# FlexEval.net
KiCad netlist of a schematic drawn in EAGLE
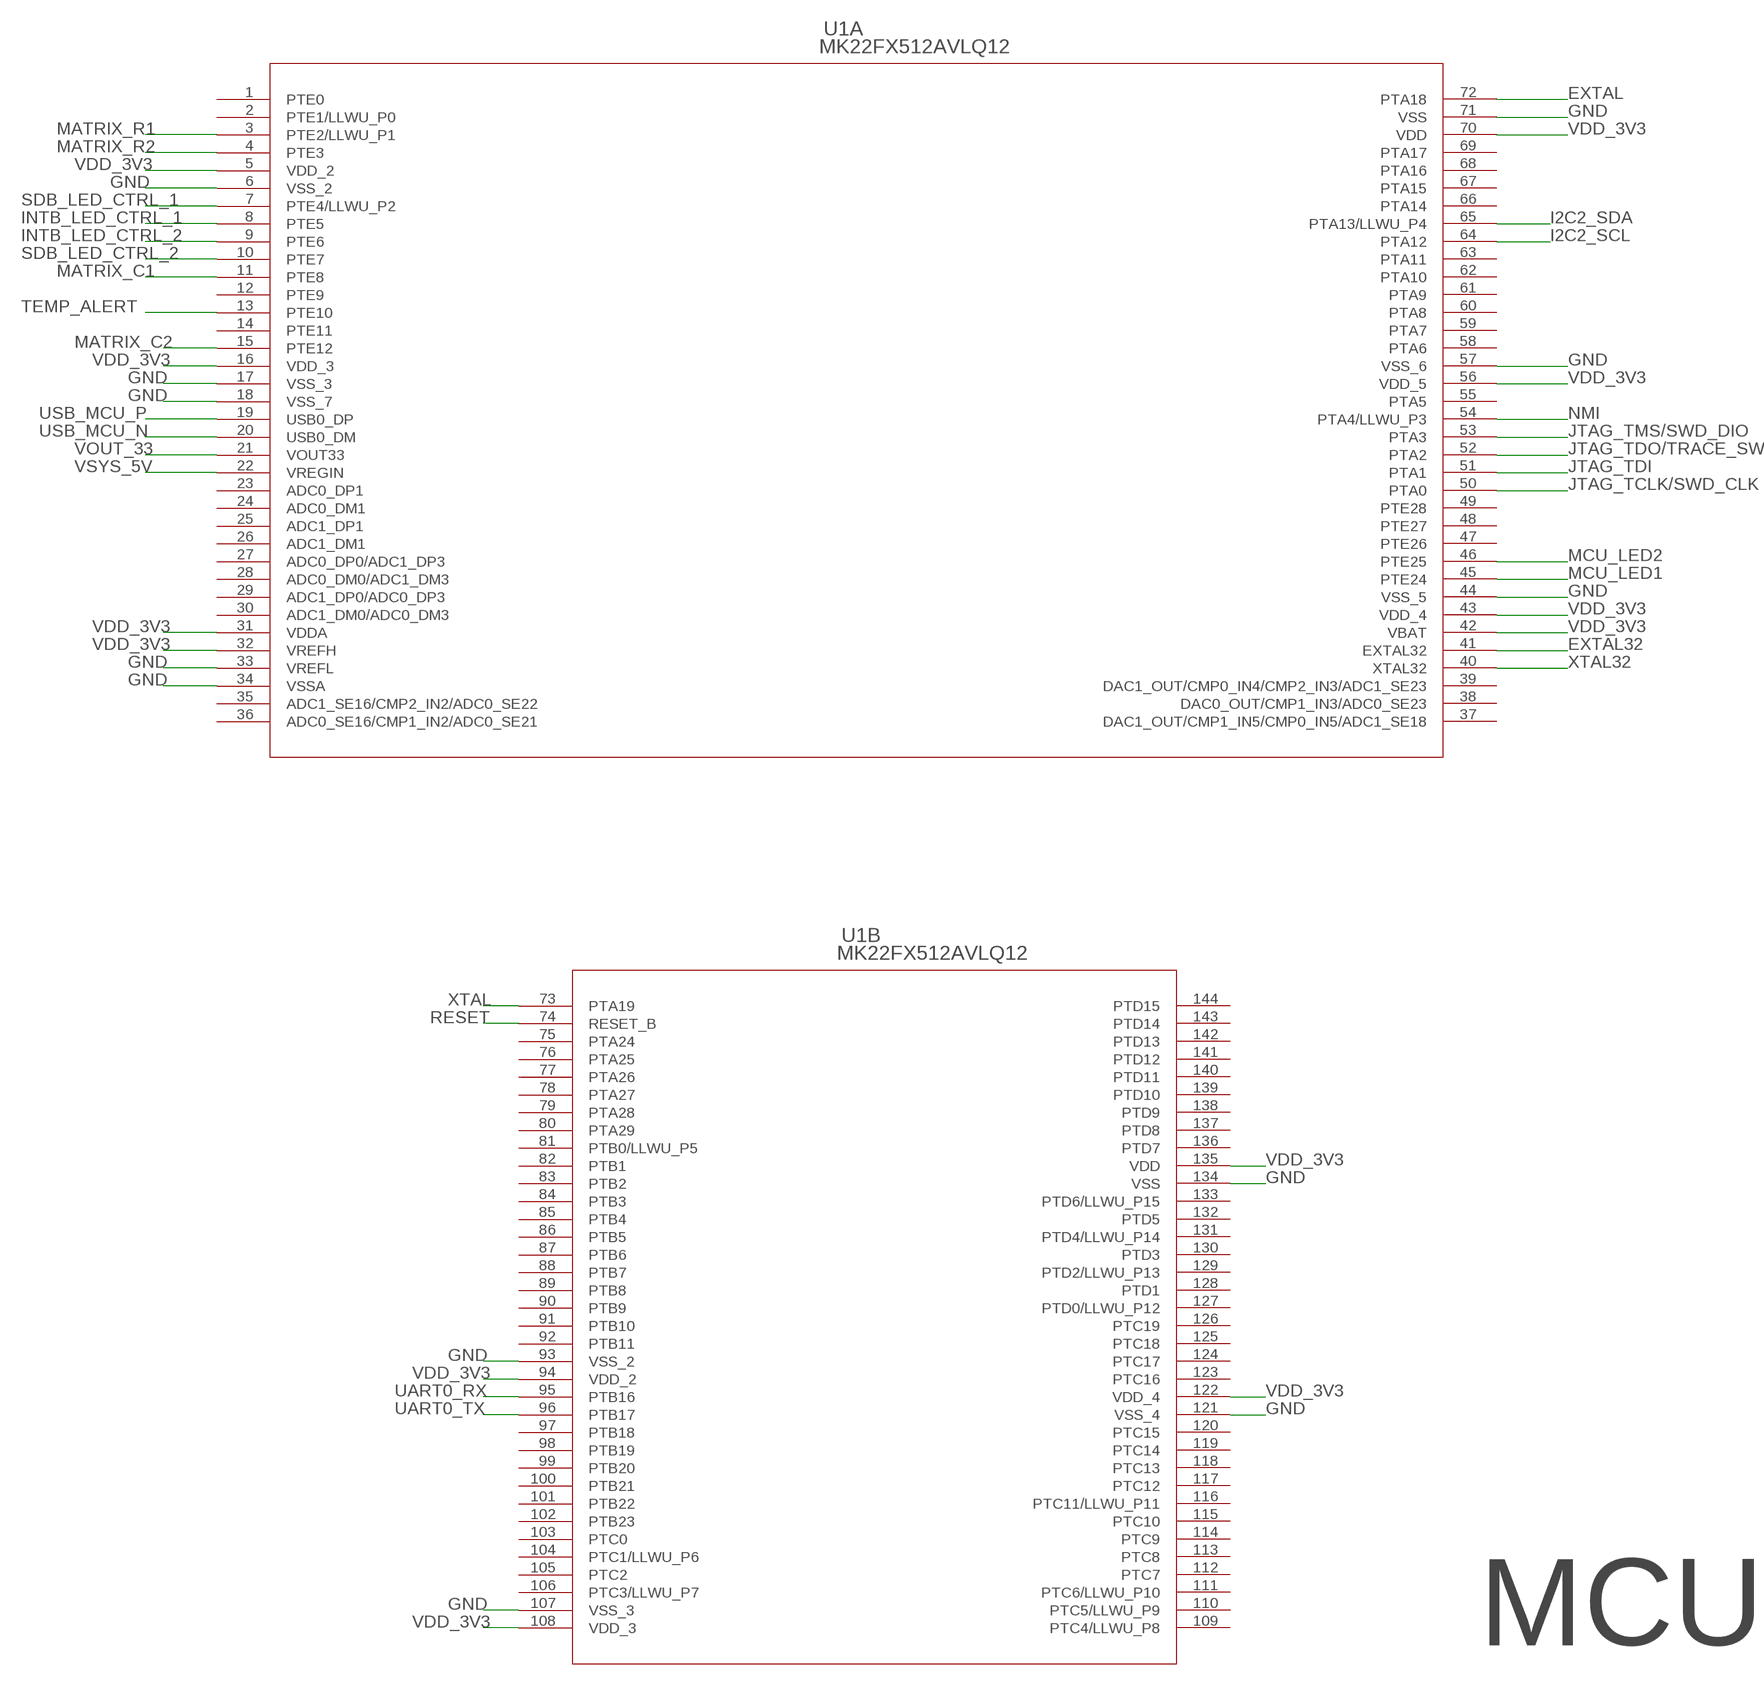
[diagram p0: schematic, sheet 1]
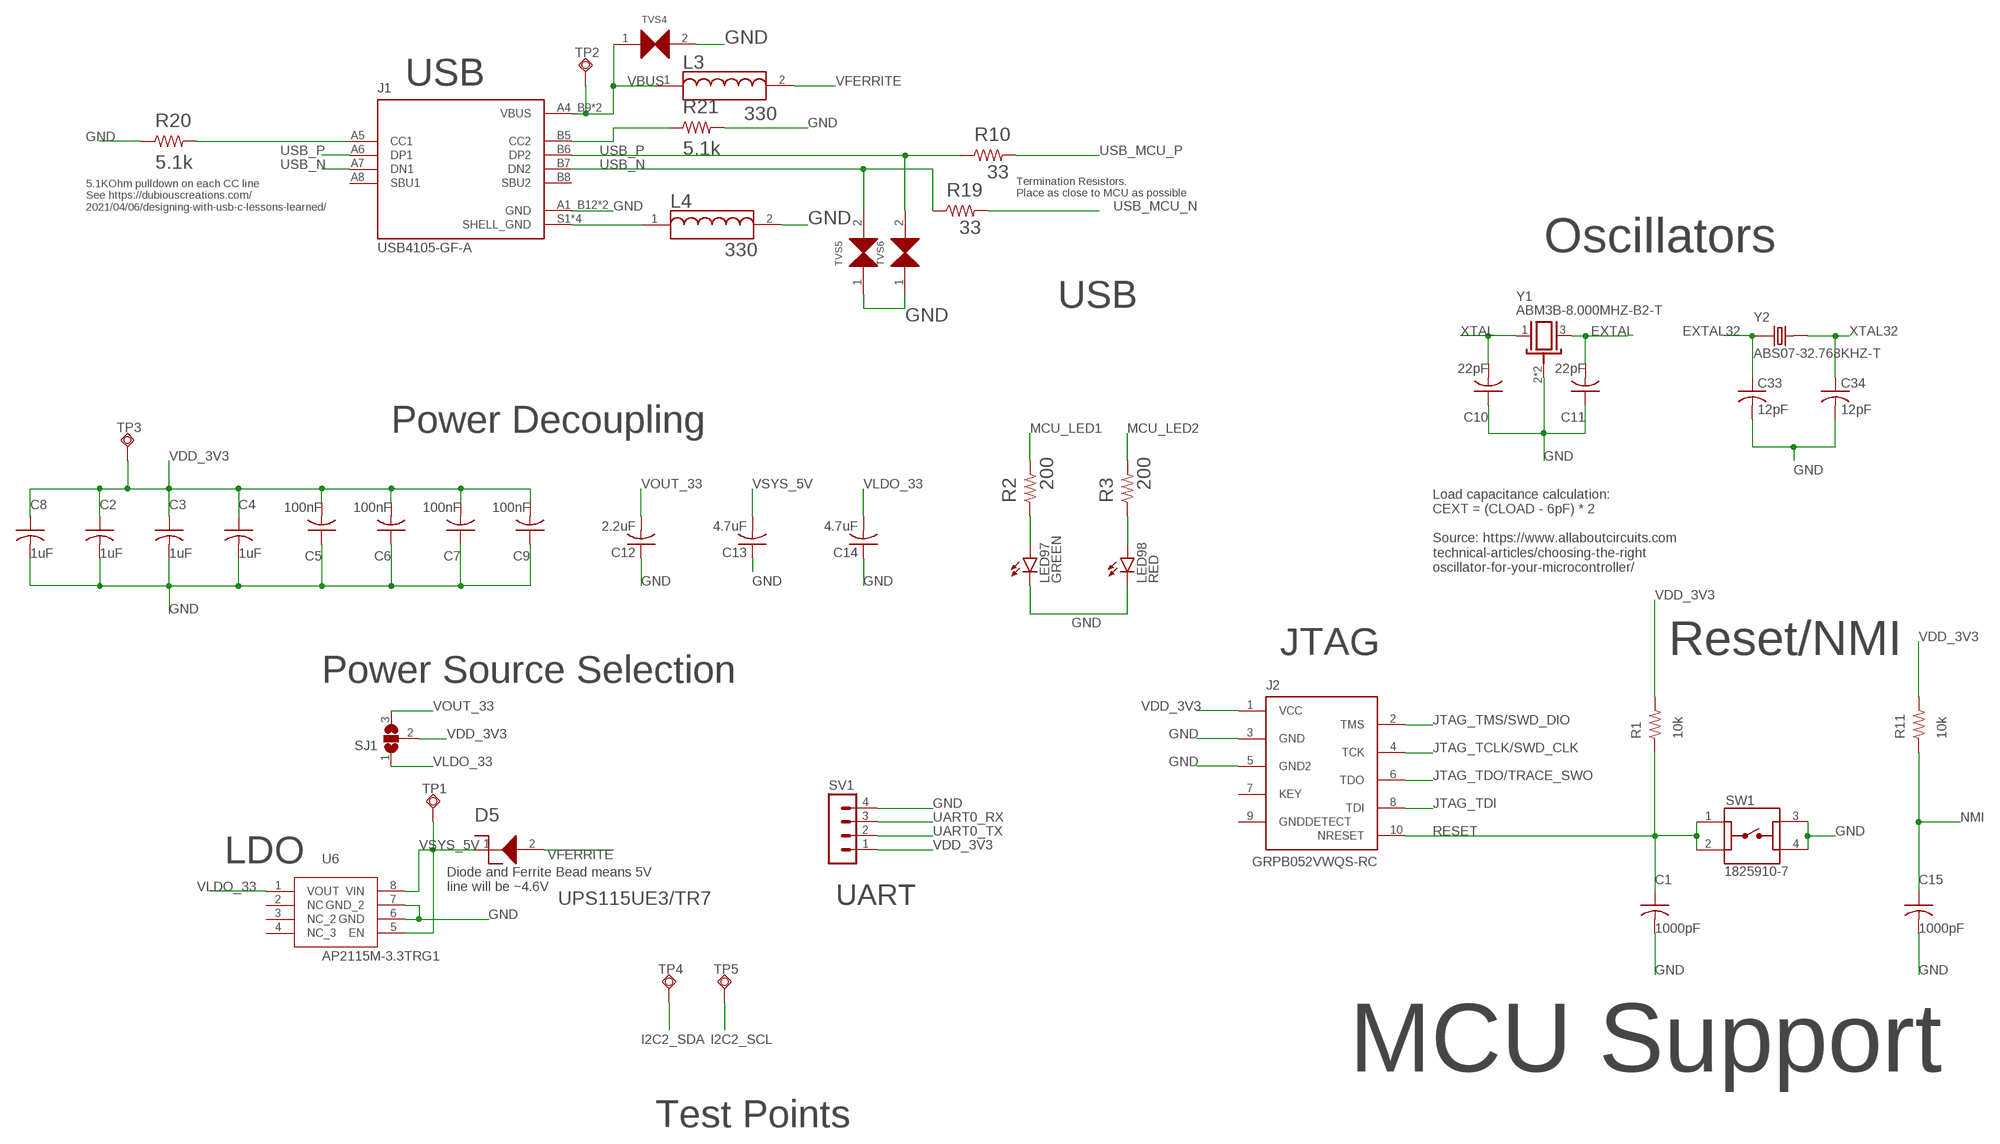
[diagram p1: schematic, sheet 2]
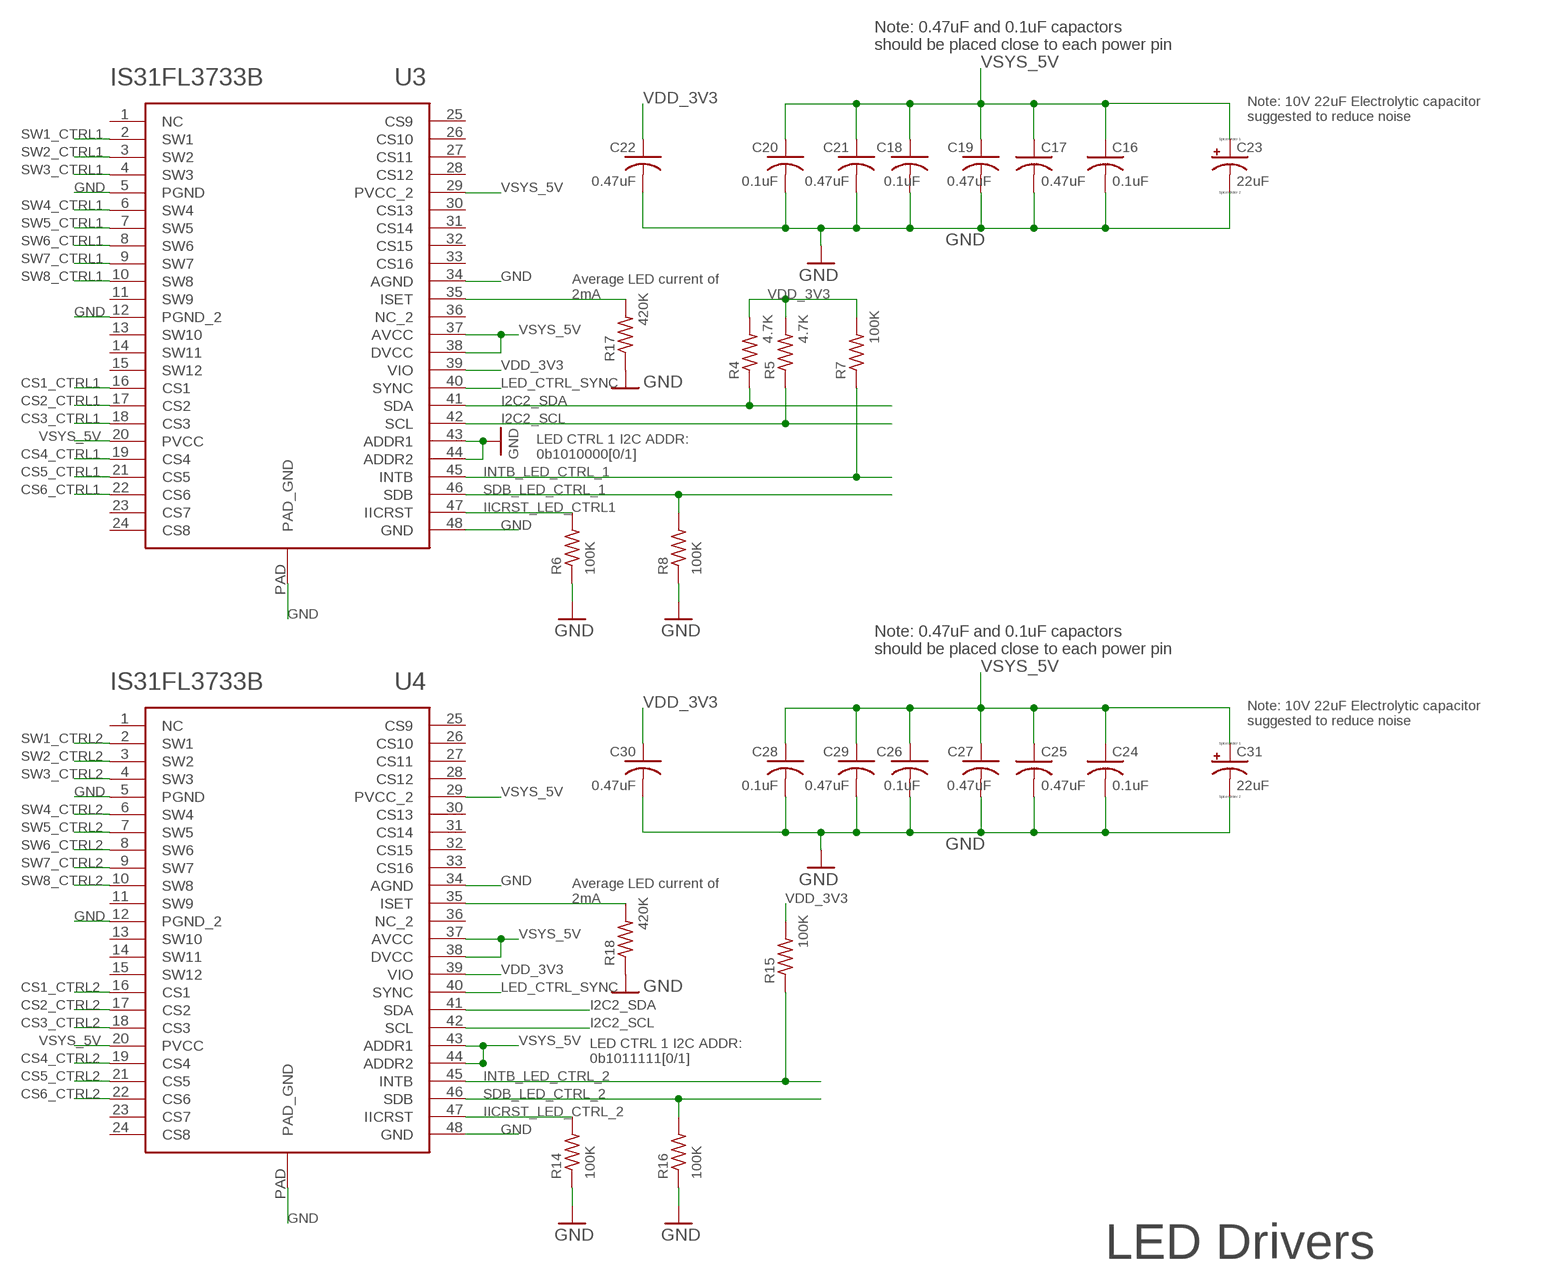
[diagram p2: schematic, sheet 3]
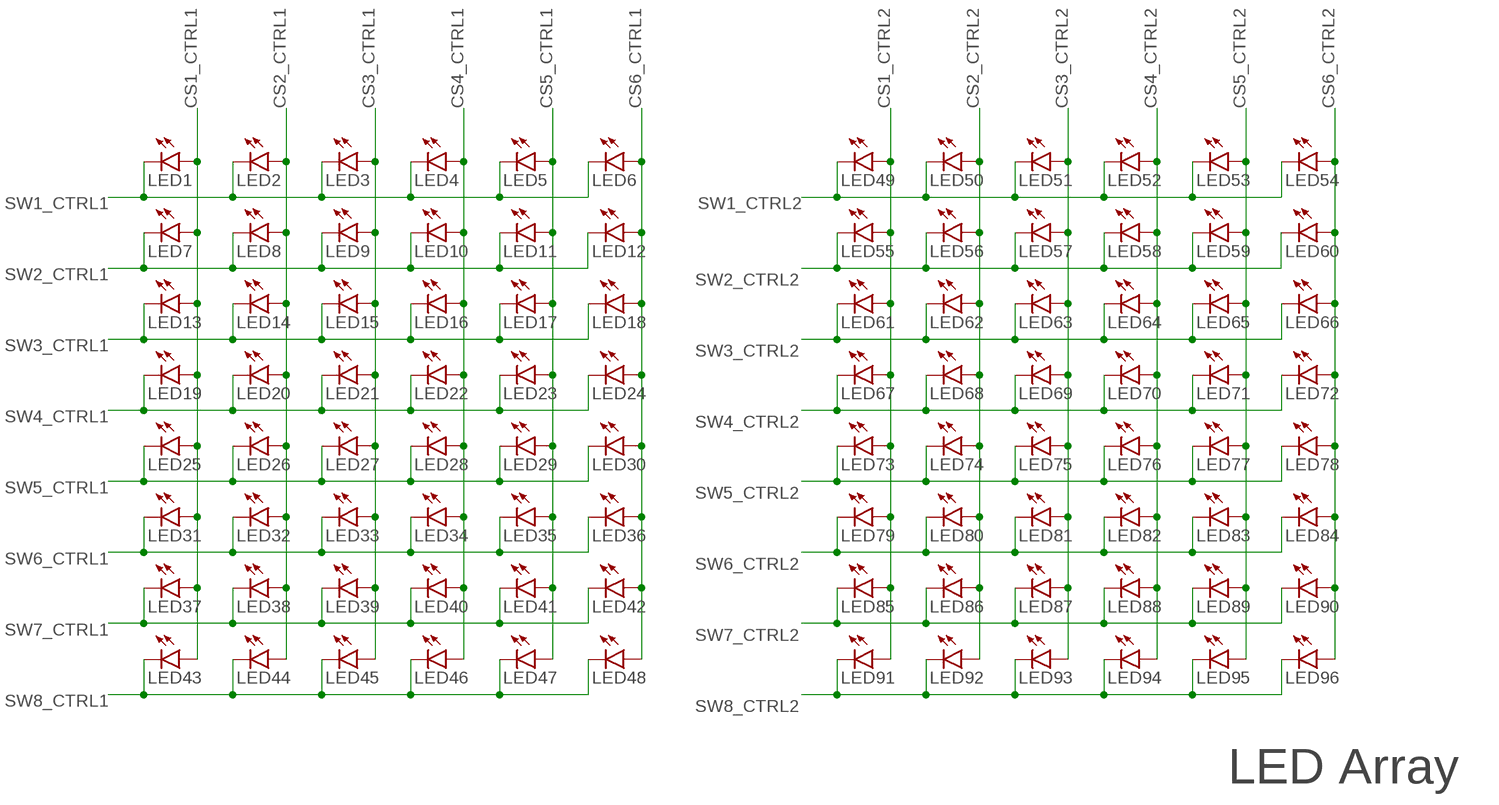
[diagram p3: schematic, sheet 4]
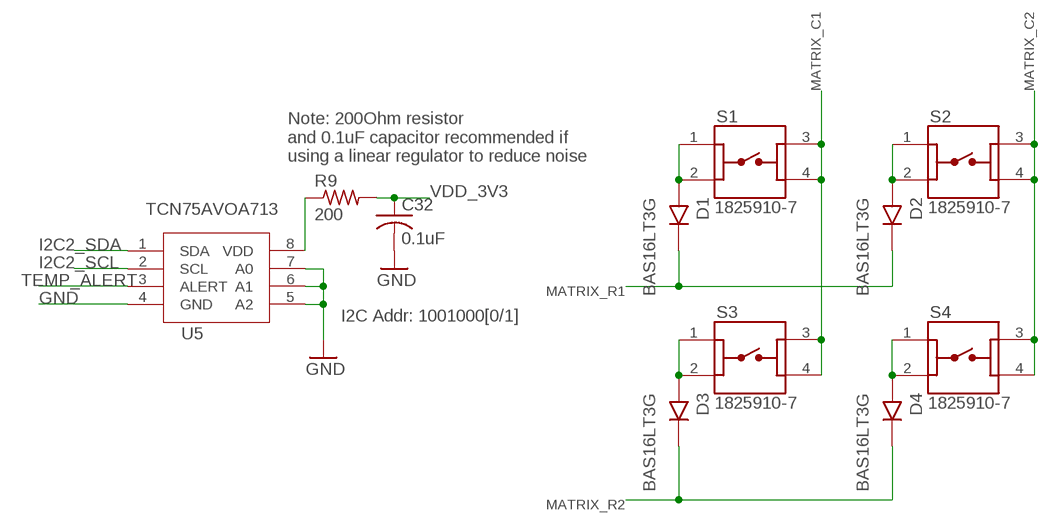
[diagram p4: schematic, sheet 5]

(export (version "E")
  (design (tool "Eeschema 10.0.6"))
  (components
    (comp (ref "C1")
      (value "1000pF")
      (footprint "eagle-import:C1206")
      (libsource (lib "eagle-import") (part "C-USC1206"))
    )
    (comp (ref "C2")
      (value "1uF")
      (footprint "eagle-import:C1206")
      (libsource (lib "eagle-import") (part "C-USC1206"))
    )
    (comp (ref "C3")
      (value "1uF")
      (footprint "eagle-import:C1206")
      (libsource (lib "eagle-import") (part "C-USC1206"))
    )
    (comp (ref "C4")
      (value "1uF")
      (footprint "eagle-import:C1206")
      (libsource (lib "eagle-import") (part "C-USC1206"))
    )
    (comp (ref "C5")
      (value "100nF")
      (footprint "eagle-import:C1206")
      (libsource (lib "eagle-import") (part "C-USC1206"))
    )
    (comp (ref "C6")
      (value "100nF")
      (footprint "eagle-import:C1206")
      (libsource (lib "eagle-import") (part "C-USC1206"))
    )
    (comp (ref "C7")
      (value "100nF")
      (footprint "eagle-import:C1206")
      (libsource (lib "eagle-import") (part "C-USC1206"))
    )
    (comp (ref "C8")
      (value "1uF")
      (footprint "eagle-import:C1206")
      (libsource (lib "eagle-import") (part "C-USC1206"))
    )
    (comp (ref "C9")
      (value "100nF")
      (footprint "eagle-import:C1206")
      (libsource (lib "eagle-import") (part "C-USC1206"))
    )
    (comp (ref "C10")
      (value "22pF")
      (footprint "eagle-import:C1206")
      (libsource (lib "eagle-import") (part "C-USC1206"))
    )
    (comp (ref "C11")
      (value "22pF")
      (footprint "eagle-import:C1206")
      (libsource (lib "eagle-import") (part "C-USC1206"))
    )
    (comp (ref "C12")
      (value "2.2uF")
      (footprint "eagle-import:C0805")
      (libsource (lib "eagle-import") (part "C-USC0805"))
    )
    (comp (ref "C13")
      (value "4.7uF")
      (footprint "eagle-import:C0805")
      (libsource (lib "eagle-import") (part "C-USC0805"))
    )
    (comp (ref "C14")
      (value "4.7uF")
      (footprint "eagle-import:C0805")
      (libsource (lib "eagle-import") (part "C-USC0805"))
    )
    (comp (ref "C15")
      (value "1000pF")
      (footprint "eagle-import:C1206")
      (libsource (lib "eagle-import") (part "C-USC1206"))
    )
    (comp (ref "C33")
      (value "12pF")
      (footprint "eagle-import:C0805")
      (libsource (lib "eagle-import") (part "C-USC0805"))
    )
    (comp (ref "C34")
      (value "12pF")
      (footprint "eagle-import:C0805")
      (libsource (lib "eagle-import") (part "C-USC0805"))
    )
    (comp (ref "D5")
      (value "UPS115UE3/TR7")
      (footprint "eagle-import:UPS115UE3_TR7")
      (libsource (lib "eagle-import") (part "UPS115UE3/TR7"))
    )
    (comp (ref "J1")
      (value "USB4105-GF-A")
      (footprint "eagle-import:GCT_USB4105-GF-A")
      (fields (field (name "MF") "GCT"))
      (libsource (lib "eagle-import") (part "USB4105-GF-A"))
    )
    (comp (ref "J2")
      (value "GRPB052VWQS-RC")
      (footprint "eagle-import:DEBUG")
      (fields (field (name "MF") "Sullins Connector"))
      (libsource (lib "eagle-import") (part "GRPB052VWQS-RC"))
    )
    (comp (ref "L3")
      (value "330")
      (footprint "eagle-import:78285333")
      (libsource (lib "eagle-import") (part "782853331SMD"))
    )
    (comp (ref "L4")
      (value "330")
      (footprint "eagle-import:78285333")
      (libsource (lib "eagle-import") (part "782853331SMD"))
    )
    (comp (ref "LED97")
      (value "GREEN")
      (footprint "eagle-import:SML1206")
      (libsource (lib "eagle-import") (part "LEDSML1206"))
    )
    (comp (ref "LED98")
      (value "RED")
      (footprint "eagle-import:SML1206")
      (libsource (lib "eagle-import") (part "LEDSML1206"))
    )
    (comp (ref "R1")
      (value "10k")
      (footprint "eagle-import:R1206")
      (libsource (lib "eagle-import") (part "R-US_R1206"))
    )
    (comp (ref "R2")
      (value "200")
      (footprint "eagle-import:R0805")
      (libsource (lib "eagle-import") (part "R-US_R0805"))
    )
    (comp (ref "R3")
      (value "200")
      (footprint "eagle-import:R0805")
      (libsource (lib "eagle-import") (part "R-US_R0805"))
    )
    (comp (ref "R10")
      (value "33")
      (footprint "eagle-import:R0805")
      (libsource (lib "eagle-import") (part "R-US_R0805"))
    )
    (comp (ref "R11")
      (value "10k")
      (footprint "eagle-import:R1206")
      (libsource (lib "eagle-import") (part "R-US_R1206"))
    )
    (comp (ref "R19")
      (value "33")
      (footprint "eagle-import:R0805")
      (libsource (lib "eagle-import") (part "R-US_R0805"))
    )
    (comp (ref "R20")
      (value "5.1k")
      (footprint "eagle-import:R0805")
      (libsource (lib "eagle-import") (part "R-US_R0805"))
    )
    (comp (ref "R21")
      (value "5.1k")
      (footprint "eagle-import:R0805")
      (libsource (lib "eagle-import") (part "R-US_R0805"))
    )
    (comp (ref "SJ1")
      (value "SJ2W")
      (footprint "eagle-import:SJ_2")
      (libsource (lib "eagle-import") (part "SJ2W"))
    )
    (comp (ref "SV1")
      (value "MA04-1")
      (footprint "eagle-import:MA04-1")
      (libsource (lib "eagle-import") (part "MA04-1"))
    )
    (comp (ref "SW1")
      (value "1825910-7")
      (footprint "eagle-import:SW_1825910-7")
      (fields (field (name "MF") "TE Connectivity"))
      (libsource (lib "eagle-import") (part "1825910-7"))
    )
    (comp (ref "TP1")
      (value "TPSQTP20R")
      (footprint "eagle-import:TP20R")
      (libsource (lib "eagle-import") (part "TPSQTP20R"))
    )
    (comp (ref "TP2")
      (value "TPSQTP20R")
      (footprint "eagle-import:TP20R")
      (libsource (lib "eagle-import") (part "TPSQTP20R"))
    )
    (comp (ref "TP3")
      (value "TPSQTP20R")
      (footprint "eagle-import:TP20R")
      (libsource (lib "eagle-import") (part "TPSQTP20R"))
    )
    (comp (ref "TP4")
      (value "TPSQTP20R")
      (footprint "eagle-import:TP20R")
      (libsource (lib "eagle-import") (part "TPSQTP20R"))
    )
    (comp (ref "TP5")
      (value "TPSQTP20R")
      (footprint "eagle-import:TP20R")
      (libsource (lib "eagle-import") (part "TPSQTP20R"))
    )
    (comp (ref "TVS4")
      (value "0603ESDA2-TR2")
      (footprint "eagle-import:0603ESDA2-TR2")
      (libsource (lib "eagle-import") (part "0603ESDA2-TR2"))
    )
    (comp (ref "TVS5")
      (value "0603ESDA2-TR2")
      (footprint "eagle-import:0603ESDA2-TR2")
      (libsource (lib "eagle-import") (part "0603ESDA2-TR2"))
    )
    (comp (ref "TVS6")
      (value "0603ESDA2-TR2")
      (footprint "eagle-import:0603ESDA2-TR2")
      (libsource (lib "eagle-import") (part "0603ESDA2-TR2"))
    )
    (comp (ref "U6")
      (value "AP2115M-3.3TRG1")
      (footprint "eagle-import:SOIC127P600X175-8N")
      (libsource (lib "eagle-import") (part "AP2115M-3.3TRG1"))
    )
    (comp (ref "Y1")
      (value "ABM3B-8.000MHZ-B2-T")
      (footprint "eagle-import:OSC_ABM3B-8.000MHZ-B2-T")
      (fields (field (name "MF") "Abracon"))
      (libsource (lib "eagle-import") (part "ABM3B-8.000MHZ-B2-T"))
    )
    (comp (ref "Y2")
      (value "ABS07-32.768KHZ-T")
      (footprint "eagle-import:XTAL_ABS07-32.768KHZ-T")
      (fields (field (name "MF") "Abracon"))
      (libsource (lib "eagle-import") (part "ABS07-32.768KHZ-T"))
    )
    (comp (ref "C32")
      (value "0.1uF")
      (footprint "eagle-import:C0805")
      (libsource (lib "eagle-import") (part "C-USC0805"))
    )
    (comp (ref "D1")
      (value "BAS16LT3G")
      (footprint "eagle-import:SOT95P240X111-3N")
      (fields (field (name "MF") "ON Semiconductor"))
      (libsource (lib "eagle-import") (part "BAS16LT3G"))
    )
    (comp (ref "D2")
      (value "BAS16LT3G")
      (footprint "eagle-import:SOT95P240X111-3N")
      (fields (field (name "MF") "ON Semiconductor"))
      (libsource (lib "eagle-import") (part "BAS16LT3G"))
    )
    (comp (ref "D3")
      (value "BAS16LT3G")
      (footprint "eagle-import:SOT95P240X111-3N")
      (fields (field (name "MF") "ON Semiconductor"))
      (libsource (lib "eagle-import") (part "BAS16LT3G"))
    )
    (comp (ref "D4")
      (value "BAS16LT3G")
      (footprint "eagle-import:SOT95P240X111-3N")
      (fields (field (name "MF") "ON Semiconductor"))
      (libsource (lib "eagle-import") (part "BAS16LT3G"))
    )
    (comp (ref "R9")
      (value "200")
      (footprint "eagle-import:R0805")
      (libsource (lib "eagle-import") (part "R-US_R0805"))
    )
    (comp (ref "S1")
      (value "1825910-7")
      (footprint "eagle-import:SW_1825910-7")
      (fields (field (name "MF") "TE Connectivity"))
      (libsource (lib "eagle-import") (part "1825910-7"))
    )
    (comp (ref "S2")
      (value "1825910-7")
      (footprint "eagle-import:SW_1825910-7")
      (fields (field (name "MF") "TE Connectivity"))
      (libsource (lib "eagle-import") (part "1825910-7"))
    )
    (comp (ref "S3")
      (value "1825910-7")
      (footprint "eagle-import:SW_1825910-7")
      (fields (field (name "MF") "TE Connectivity"))
      (libsource (lib "eagle-import") (part "1825910-7"))
    )
    (comp (ref "S4")
      (value "1825910-7")
      (footprint "eagle-import:SW_1825910-7")
      (fields (field (name "MF") "TE Connectivity"))
      (libsource (lib "eagle-import") (part "1825910-7"))
    )
    (comp (ref "U5")
      (value "SOIC127P600X175-8N")
      (footprint "eagle-import:SOIC127P600X175-8N")
      (fields (field (name "MANUFACTURER") "hotchip"))
      (libsource (lib "eagle-import") (part "SOIC127P600X175-8N"))
    )
    (comp (ref "U1")
      (value "MK22FX512AVLQ12")
      (footprint "eagle-import:LQFP-144_20X20X1.6")
      (libsource (lib "eagle-import") (part "MK22FX512AVLQ12"))
    )
    (comp (ref "C16")
      (value "0.1uF")
      (footprint "eagle-import:C0805")
      (libsource (lib "eagle-import") (part "C-USC0805"))
    )
    (comp (ref "C17")
      (value "0.47uF")
      (footprint "eagle-import:C0805")
      (libsource (lib "eagle-import") (part "C-USC0805"))
    )
    (comp (ref "C18")
      (value "0.1uF")
      (footprint "eagle-import:C0805")
      (libsource (lib "eagle-import") (part "C-USC0805"))
    )
    (comp (ref "C19")
      (value "0.47uF")
      (footprint "eagle-import:C0805")
      (libsource (lib "eagle-import") (part "C-USC0805"))
    )
    (comp (ref "C20")
      (value "0.1uF")
      (footprint "eagle-import:C0805")
      (libsource (lib "eagle-import") (part "C-USC0805"))
    )
    (comp (ref "C21")
      (value "0.47uF")
      (footprint "eagle-import:C0805")
      (libsource (lib "eagle-import") (part "C-USC0805"))
    )
    (comp (ref "C22")
      (value "0.47uF")
      (footprint "eagle-import:C0805")
      (libsource (lib "eagle-import") (part "C-USC0805"))
    )
    (comp (ref "C23")
      (value "22uF")
      (footprint "eagle-import:860020672011")
      (libsource (lib "eagle-import") (part "860020672011"))
    )
    (comp (ref "C24")
      (value "0.1uF")
      (footprint "eagle-import:C0805")
      (libsource (lib "eagle-import") (part "C-USC0805"))
    )
    (comp (ref "C25")
      (value "0.47uF")
      (footprint "eagle-import:C0805")
      (libsource (lib "eagle-import") (part "C-USC0805"))
    )
    (comp (ref "C26")
      (value "0.1uF")
      (footprint "eagle-import:C0805")
      (libsource (lib "eagle-import") (part "C-USC0805"))
    )
    (comp (ref "C27")
      (value "0.47uF")
      (footprint "eagle-import:C0805")
      (libsource (lib "eagle-import") (part "C-USC0805"))
    )
    (comp (ref "C28")
      (value "0.1uF")
      (footprint "eagle-import:C0805")
      (libsource (lib "eagle-import") (part "C-USC0805"))
    )
    (comp (ref "C29")
      (value "0.47uF")
      (footprint "eagle-import:C0805")
      (libsource (lib "eagle-import") (part "C-USC0805"))
    )
    (comp (ref "C30")
      (value "0.47uF")
      (footprint "eagle-import:C0805")
      (libsource (lib "eagle-import") (part "C-USC0805"))
    )
    (comp (ref "C31")
      (value "22uF")
      (footprint "eagle-import:860020672011")
      (libsource (lib "eagle-import") (part "860020672011"))
    )
    (comp (ref "R4")
      (value "4.7K")
      (footprint "eagle-import:R0805")
      (libsource (lib "eagle-import") (part "R-US_R0805"))
    )
    (comp (ref "R5")
      (value "4.7K")
      (footprint "eagle-import:R0805")
      (libsource (lib "eagle-import") (part "R-US_R0805"))
    )
    (comp (ref "R6")
      (value "100K")
      (footprint "eagle-import:R0805")
      (libsource (lib "eagle-import") (part "R-US_R0805"))
    )
    (comp (ref "R7")
      (value "100K")
      (footprint "eagle-import:R0805")
      (libsource (lib "eagle-import") (part "R-US_R0805"))
    )
    (comp (ref "R8")
      (value "100K")
      (footprint "eagle-import:R0805")
      (libsource (lib "eagle-import") (part "R-US_R0805"))
    )
    (comp (ref "R14")
      (value "100K")
      (footprint "eagle-import:R0805")
      (libsource (lib "eagle-import") (part "R-US_R0805"))
    )
    (comp (ref "R15")
      (value "100K")
      (footprint "eagle-import:R0805")
      (libsource (lib "eagle-import") (part "R-US_R0805"))
    )
    (comp (ref "R16")
      (value "100K")
      (footprint "eagle-import:R0805")
      (libsource (lib "eagle-import") (part "R-US_R0805"))
    )
    (comp (ref "R17")
      (value "420K")
      (footprint "eagle-import:R0805")
      (libsource (lib "eagle-import") (part "R-US_R0805"))
    )
    (comp (ref "R18")
      (value "420K")
      (footprint "eagle-import:R0805")
      (libsource (lib "eagle-import") (part "R-US_R0805"))
    )
    (comp (ref "U3")
      (value "IS31FL3733B-TQLS4")
      (footprint "eagle-import:IS31FL3733B-TQLS4")
      (libsource (lib "eagle-import") (part "IS31FL3733B-TQLS4"))
    )
    (comp (ref "U4")
      (value "IS31FL3733B-TQLS4")
      (footprint "eagle-import:IS31FL3733B-TQLS4")
      (libsource (lib "eagle-import") (part "IS31FL3733B-TQLS4"))
    )
    (comp (ref "LED1")
      (value "LED3MM")
      (footprint "eagle-import:LED3MM")
      (libsource (lib "eagle-import") (part "LED3MM"))
    )
    (comp (ref "LED2")
      (value "LED3MM")
      (footprint "eagle-import:LED3MM")
      (libsource (lib "eagle-import") (part "LED3MM"))
    )
    (comp (ref "LED3")
      (value "LED3MM")
      (footprint "eagle-import:LED3MM")
      (libsource (lib "eagle-import") (part "LED3MM"))
    )
    (comp (ref "LED4")
      (value "LED3MM")
      (footprint "eagle-import:LED3MM")
      (libsource (lib "eagle-import") (part "LED3MM"))
    )
    (comp (ref "LED5")
      (value "LED3MM")
      (footprint "eagle-import:LED3MM")
      (libsource (lib "eagle-import") (part "LED3MM"))
    )
    (comp (ref "LED6")
      (value "LED3MM")
      (footprint "eagle-import:LED3MM")
      (libsource (lib "eagle-import") (part "LED3MM"))
    )
    (comp (ref "LED7")
      (value "LED3MM")
      (footprint "eagle-import:LED3MM")
      (libsource (lib "eagle-import") (part "LED3MM"))
    )
    (comp (ref "LED8")
      (value "LED3MM")
      (footprint "eagle-import:LED3MM")
      (libsource (lib "eagle-import") (part "LED3MM"))
    )
    (comp (ref "LED9")
      (value "LED3MM")
      (footprint "eagle-import:LED3MM")
      (libsource (lib "eagle-import") (part "LED3MM"))
    )
    (comp (ref "LED10")
      (value "LED3MM")
      (footprint "eagle-import:LED3MM")
      (libsource (lib "eagle-import") (part "LED3MM"))
    )
    (comp (ref "LED11")
      (value "LED3MM")
      (footprint "eagle-import:LED3MM")
      (libsource (lib "eagle-import") (part "LED3MM"))
    )
    (comp (ref "LED12")
      (value "LED3MM")
      (footprint "eagle-import:LED3MM")
      (libsource (lib "eagle-import") (part "LED3MM"))
    )
    (comp (ref "LED13")
      (value "LED3MM")
      (footprint "eagle-import:LED3MM")
      (libsource (lib "eagle-import") (part "LED3MM"))
    )
    (comp (ref "LED14")
      (value "LED3MM")
      (footprint "eagle-import:LED3MM")
      (libsource (lib "eagle-import") (part "LED3MM"))
    )
    (comp (ref "LED15")
      (value "LED3MM")
      (footprint "eagle-import:LED3MM")
      (libsource (lib "eagle-import") (part "LED3MM"))
    )
    (comp (ref "LED16")
      (value "LED3MM")
      (footprint "eagle-import:LED3MM")
      (libsource (lib "eagle-import") (part "LED3MM"))
    )
    (comp (ref "LED17")
      (value "LED3MM")
      (footprint "eagle-import:LED3MM")
      (libsource (lib "eagle-import") (part "LED3MM"))
    )
    (comp (ref "LED18")
      (value "LED3MM")
      (footprint "eagle-import:LED3MM")
      (libsource (lib "eagle-import") (part "LED3MM"))
    )
    (comp (ref "LED19")
      (value "LED3MM")
      (footprint "eagle-import:LED3MM")
      (libsource (lib "eagle-import") (part "LED3MM"))
    )
    (comp (ref "LED20")
      (value "LED3MM")
      (footprint "eagle-import:LED3MM")
      (libsource (lib "eagle-import") (part "LED3MM"))
    )
    (comp (ref "LED21")
      (value "LED3MM")
      (footprint "eagle-import:LED3MM")
      (libsource (lib "eagle-import") (part "LED3MM"))
    )
    (comp (ref "LED22")
      (value "LED3MM")
      (footprint "eagle-import:LED3MM")
      (libsource (lib "eagle-import") (part "LED3MM"))
    )
    (comp (ref "LED23")
      (value "LED3MM")
      (footprint "eagle-import:LED3MM")
      (libsource (lib "eagle-import") (part "LED3MM"))
    )
    (comp (ref "LED24")
      (value "LED3MM")
      (footprint "eagle-import:LED3MM")
      (libsource (lib "eagle-import") (part "LED3MM"))
    )
    (comp (ref "LED25")
      (value "LED3MM")
      (footprint "eagle-import:LED3MM")
      (libsource (lib "eagle-import") (part "LED3MM"))
    )
    (comp (ref "LED26")
      (value "LED3MM")
      (footprint "eagle-import:LED3MM")
      (libsource (lib "eagle-import") (part "LED3MM"))
    )
    (comp (ref "LED27")
      (value "LED3MM")
      (footprint "eagle-import:LED3MM")
      (libsource (lib "eagle-import") (part "LED3MM"))
    )
    (comp (ref "LED28")
      (value "LED3MM")
      (footprint "eagle-import:LED3MM")
      (libsource (lib "eagle-import") (part "LED3MM"))
    )
    (comp (ref "LED29")
      (value "LED3MM")
      (footprint "eagle-import:LED3MM")
      (libsource (lib "eagle-import") (part "LED3MM"))
    )
    (comp (ref "LED30")
      (value "LED3MM")
      (footprint "eagle-import:LED3MM")
      (libsource (lib "eagle-import") (part "LED3MM"))
    )
    (comp (ref "LED31")
      (value "LED3MM")
      (footprint "eagle-import:LED3MM")
      (libsource (lib "eagle-import") (part "LED3MM"))
    )
    (comp (ref "LED32")
      (value "LED3MM")
      (footprint "eagle-import:LED3MM")
      (libsource (lib "eagle-import") (part "LED3MM"))
    )
    (comp (ref "LED33")
      (value "LED3MM")
      (footprint "eagle-import:LED3MM")
      (libsource (lib "eagle-import") (part "LED3MM"))
    )
    (comp (ref "LED34")
      (value "LED3MM")
      (footprint "eagle-import:LED3MM")
      (libsource (lib "eagle-import") (part "LED3MM"))
    )
    (comp (ref "LED35")
      (value "LED3MM")
      (footprint "eagle-import:LED3MM")
      (libsource (lib "eagle-import") (part "LED3MM"))
    )
    (comp (ref "LED36")
      (value "LED3MM")
      (footprint "eagle-import:LED3MM")
      (libsource (lib "eagle-import") (part "LED3MM"))
    )
    (comp (ref "LED37")
      (value "LED3MM")
      (footprint "eagle-import:LED3MM")
      (libsource (lib "eagle-import") (part "LED3MM"))
    )
    (comp (ref "LED38")
      (value "LED3MM")
      (footprint "eagle-import:LED3MM")
      (libsource (lib "eagle-import") (part "LED3MM"))
    )
    (comp (ref "LED39")
      (value "LED3MM")
      (footprint "eagle-import:LED3MM")
      (libsource (lib "eagle-import") (part "LED3MM"))
    )
    (comp (ref "LED40")
      (value "LED3MM")
      (footprint "eagle-import:LED3MM")
      (libsource (lib "eagle-import") (part "LED3MM"))
    )
    (comp (ref "LED41")
      (value "LED3MM")
      (footprint "eagle-import:LED3MM")
      (libsource (lib "eagle-import") (part "LED3MM"))
    )
    (comp (ref "LED42")
      (value "LED3MM")
      (footprint "eagle-import:LED3MM")
      (libsource (lib "eagle-import") (part "LED3MM"))
    )
    (comp (ref "LED43")
      (value "LED3MM")
      (footprint "eagle-import:LED3MM")
      (libsource (lib "eagle-import") (part "LED3MM"))
    )
    (comp (ref "LED44")
      (value "LED3MM")
      (footprint "eagle-import:LED3MM")
      (libsource (lib "eagle-import") (part "LED3MM"))
    )
    (comp (ref "LED45")
      (value "LED3MM")
      (footprint "eagle-import:LED3MM")
      (libsource (lib "eagle-import") (part "LED3MM"))
    )
    (comp (ref "LED46")
      (value "LED3MM")
      (footprint "eagle-import:LED3MM")
      (libsource (lib "eagle-import") (part "LED3MM"))
    )
    (comp (ref "LED47")
      (value "LED3MM")
      (footprint "eagle-import:LED3MM")
      (libsource (lib "eagle-import") (part "LED3MM"))
    )
    (comp (ref "LED48")
      (value "LED3MM")
      (footprint "eagle-import:LED3MM")
      (libsource (lib "eagle-import") (part "LED3MM"))
    )
    (comp (ref "LED49")
      (value "LED3MM")
      (footprint "eagle-import:LED3MM")
      (libsource (lib "eagle-import") (part "LED3MM"))
    )
    (comp (ref "LED50")
      (value "LED3MM")
      (footprint "eagle-import:LED3MM")
      (libsource (lib "eagle-import") (part "LED3MM"))
    )
    (comp (ref "LED51")
      (value "LED3MM")
      (footprint "eagle-import:LED3MM")
      (libsource (lib "eagle-import") (part "LED3MM"))
    )
    (comp (ref "LED52")
      (value "LED3MM")
      (footprint "eagle-import:LED3MM")
      (libsource (lib "eagle-import") (part "LED3MM"))
    )
    (comp (ref "LED53")
      (value "LED3MM")
      (footprint "eagle-import:LED3MM")
      (libsource (lib "eagle-import") (part "LED3MM"))
    )
    (comp (ref "LED54")
      (value "LED3MM")
      (footprint "eagle-import:LED3MM")
      (libsource (lib "eagle-import") (part "LED3MM"))
    )
    (comp (ref "LED55")
      (value "LED3MM")
      (footprint "eagle-import:LED3MM")
      (libsource (lib "eagle-import") (part "LED3MM"))
    )
    (comp (ref "LED56")
      (value "LED3MM")
      (footprint "eagle-import:LED3MM")
      (libsource (lib "eagle-import") (part "LED3MM"))
    )
    (comp (ref "LED57")
      (value "LED3MM")
      (footprint "eagle-import:LED3MM")
      (libsource (lib "eagle-import") (part "LED3MM"))
    )
    (comp (ref "LED58")
      (value "LED3MM")
      (footprint "eagle-import:LED3MM")
      (libsource (lib "eagle-import") (part "LED3MM"))
    )
    (comp (ref "LED59")
      (value "LED3MM")
      (footprint "eagle-import:LED3MM")
      (libsource (lib "eagle-import") (part "LED3MM"))
    )
    (comp (ref "LED60")
      (value "LED3MM")
      (footprint "eagle-import:LED3MM")
      (libsource (lib "eagle-import") (part "LED3MM"))
    )
    (comp (ref "LED61")
      (value "LED3MM")
      (footprint "eagle-import:LED3MM")
      (libsource (lib "eagle-import") (part "LED3MM"))
    )
    (comp (ref "LED62")
      (value "LED3MM")
      (footprint "eagle-import:LED3MM")
      (libsource (lib "eagle-import") (part "LED3MM"))
    )
    (comp (ref "LED63")
      (value "LED3MM")
      (footprint "eagle-import:LED3MM")
      (libsource (lib "eagle-import") (part "LED3MM"))
    )
    (comp (ref "LED64")
      (value "LED3MM")
      (footprint "eagle-import:LED3MM")
      (libsource (lib "eagle-import") (part "LED3MM"))
    )
    (comp (ref "LED65")
      (value "LED3MM")
      (footprint "eagle-import:LED3MM")
      (libsource (lib "eagle-import") (part "LED3MM"))
    )
    (comp (ref "LED66")
      (value "LED3MM")
      (footprint "eagle-import:LED3MM")
      (libsource (lib "eagle-import") (part "LED3MM"))
    )
    (comp (ref "LED67")
      (value "LED3MM")
      (footprint "eagle-import:LED3MM")
      (libsource (lib "eagle-import") (part "LED3MM"))
    )
    (comp (ref "LED68")
      (value "LED3MM")
      (footprint "eagle-import:LED3MM")
      (libsource (lib "eagle-import") (part "LED3MM"))
    )
    (comp (ref "LED69")
      (value "LED3MM")
      (footprint "eagle-import:LED3MM")
      (libsource (lib "eagle-import") (part "LED3MM"))
    )
    (comp (ref "LED70")
      (value "LED3MM")
      (footprint "eagle-import:LED3MM")
      (libsource (lib "eagle-import") (part "LED3MM"))
    )
    (comp (ref "LED71")
      (value "LED3MM")
      (footprint "eagle-import:LED3MM")
      (libsource (lib "eagle-import") (part "LED3MM"))
    )
    (comp (ref "LED72")
      (value "LED3MM")
      (footprint "eagle-import:LED3MM")
      (libsource (lib "eagle-import") (part "LED3MM"))
    )
    (comp (ref "LED73")
      (value "LED3MM")
      (footprint "eagle-import:LED3MM")
      (libsource (lib "eagle-import") (part "LED3MM"))
    )
    (comp (ref "LED74")
      (value "LED3MM")
      (footprint "eagle-import:LED3MM")
      (libsource (lib "eagle-import") (part "LED3MM"))
    )
    (comp (ref "LED75")
      (value "LED3MM")
      (footprint "eagle-import:LED3MM")
      (libsource (lib "eagle-import") (part "LED3MM"))
    )
    (comp (ref "LED76")
      (value "LED3MM")
      (footprint "eagle-import:LED3MM")
      (libsource (lib "eagle-import") (part "LED3MM"))
    )
    (comp (ref "LED77")
      (value "LED3MM")
      (footprint "eagle-import:LED3MM")
      (libsource (lib "eagle-import") (part "LED3MM"))
    )
    (comp (ref "LED78")
      (value "LED3MM")
      (footprint "eagle-import:LED3MM")
      (libsource (lib "eagle-import") (part "LED3MM"))
    )
    (comp (ref "LED79")
      (value "LED3MM")
      (footprint "eagle-import:LED3MM")
      (libsource (lib "eagle-import") (part "LED3MM"))
    )
    (comp (ref "LED80")
      (value "LED3MM")
      (footprint "eagle-import:LED3MM")
      (libsource (lib "eagle-import") (part "LED3MM"))
    )
    (comp (ref "LED81")
      (value "LED3MM")
      (footprint "eagle-import:LED3MM")
      (libsource (lib "eagle-import") (part "LED3MM"))
    )
    (comp (ref "LED82")
      (value "LED3MM")
      (footprint "eagle-import:LED3MM")
      (libsource (lib "eagle-import") (part "LED3MM"))
    )
    (comp (ref "LED83")
      (value "LED3MM")
      (footprint "eagle-import:LED3MM")
      (libsource (lib "eagle-import") (part "LED3MM"))
    )
    (comp (ref "LED84")
      (value "LED3MM")
      (footprint "eagle-import:LED3MM")
      (libsource (lib "eagle-import") (part "LED3MM"))
    )
    (comp (ref "LED85")
      (value "LED3MM")
      (footprint "eagle-import:LED3MM")
      (libsource (lib "eagle-import") (part "LED3MM"))
    )
    (comp (ref "LED86")
      (value "LED3MM")
      (footprint "eagle-import:LED3MM")
      (libsource (lib "eagle-import") (part "LED3MM"))
    )
    (comp (ref "LED87")
      (value "LED3MM")
      (footprint "eagle-import:LED3MM")
      (libsource (lib "eagle-import") (part "LED3MM"))
    )
    (comp (ref "LED88")
      (value "LED3MM")
      (footprint "eagle-import:LED3MM")
      (libsource (lib "eagle-import") (part "LED3MM"))
    )
    (comp (ref "LED89")
      (value "LED3MM")
      (footprint "eagle-import:LED3MM")
      (libsource (lib "eagle-import") (part "LED3MM"))
    )
    (comp (ref "LED90")
      (value "LED3MM")
      (footprint "eagle-import:LED3MM")
      (libsource (lib "eagle-import") (part "LED3MM"))
    )
    (comp (ref "LED91")
      (value "LED3MM")
      (footprint "eagle-import:LED3MM")
      (libsource (lib "eagle-import") (part "LED3MM"))
    )
    (comp (ref "LED92")
      (value "LED3MM")
      (footprint "eagle-import:LED3MM")
      (libsource (lib "eagle-import") (part "LED3MM"))
    )
    (comp (ref "LED93")
      (value "LED3MM")
      (footprint "eagle-import:LED3MM")
      (libsource (lib "eagle-import") (part "LED3MM"))
    )
    (comp (ref "LED94")
      (value "LED3MM")
      (footprint "eagle-import:LED3MM")
      (libsource (lib "eagle-import") (part "LED3MM"))
    )
    (comp (ref "LED95")
      (value "LED3MM")
      (footprint "eagle-import:LED3MM")
      (libsource (lib "eagle-import") (part "LED3MM"))
    )
    (comp (ref "LED96")
      (value "LED3MM")
      (footprint "eagle-import:LED3MM")
      (libsource (lib "eagle-import") (part "LED3MM"))
    )
  )
  (nets
    (net (code "1") (name "CS1_CTRL1") (class "Default")
      (node (ref "LED1") (pin "A") (pinfunction "A_A") (pintype "passive"))
      (node (ref "LED13") (pin "A") (pinfunction "A_A") (pintype "passive"))
      (node (ref "LED19") (pin "A") (pinfunction "A_A") (pintype "passive"))
      (node (ref "LED25") (pin "A") (pinfunction "A_A") (pintype "passive"))
      (node (ref "LED31") (pin "A") (pinfunction "A_A") (pintype "passive"))
      (node (ref "LED37") (pin "A") (pinfunction "A_A") (pintype "passive"))
      (node (ref "LED43") (pin "A") (pinfunction "A_A") (pintype "passive"))
      (node (ref "LED7") (pin "A") (pinfunction "A_A") (pintype "passive"))
      (node (ref "U3") (pin "16") (pinfunction "CS1_16") (pintype "bidirectional"))
    )
    (net (code "2") (name "CS1_CTRL2") (class "Default")
      (node (ref "LED49") (pin "A") (pinfunction "A_A") (pintype "passive"))
      (node (ref "LED55") (pin "A") (pinfunction "A_A") (pintype "passive"))
      (node (ref "LED61") (pin "A") (pinfunction "A_A") (pintype "passive"))
      (node (ref "LED67") (pin "A") (pinfunction "A_A") (pintype "passive"))
      (node (ref "LED73") (pin "A") (pinfunction "A_A") (pintype "passive"))
      (node (ref "LED79") (pin "A") (pinfunction "A_A") (pintype "passive"))
      (node (ref "LED85") (pin "A") (pinfunction "A_A") (pintype "passive"))
      (node (ref "LED91") (pin "A") (pinfunction "A_A") (pintype "passive"))
      (node (ref "U4") (pin "16") (pinfunction "CS1_16") (pintype "bidirectional"))
    )
    (net (code "3") (name "CS2_CTRL1") (class "Default")
      (node (ref "LED14") (pin "A") (pinfunction "A_A") (pintype "passive"))
      (node (ref "LED2") (pin "A") (pinfunction "A_A") (pintype "passive"))
      (node (ref "LED20") (pin "A") (pinfunction "A_A") (pintype "passive"))
      (node (ref "LED26") (pin "A") (pinfunction "A_A") (pintype "passive"))
      (node (ref "LED32") (pin "A") (pinfunction "A_A") (pintype "passive"))
      (node (ref "LED38") (pin "A") (pinfunction "A_A") (pintype "passive"))
      (node (ref "LED44") (pin "A") (pinfunction "A_A") (pintype "passive"))
      (node (ref "LED8") (pin "A") (pinfunction "A_A") (pintype "passive"))
      (node (ref "U3") (pin "17") (pinfunction "CS2_17") (pintype "bidirectional"))
    )
    (net (code "4") (name "CS2_CTRL2") (class "Default")
      (node (ref "LED50") (pin "A") (pinfunction "A_A") (pintype "passive"))
      (node (ref "LED56") (pin "A") (pinfunction "A_A") (pintype "passive"))
      (node (ref "LED62") (pin "A") (pinfunction "A_A") (pintype "passive"))
      (node (ref "LED68") (pin "A") (pinfunction "A_A") (pintype "passive"))
      (node (ref "LED74") (pin "A") (pinfunction "A_A") (pintype "passive"))
      (node (ref "LED80") (pin "A") (pinfunction "A_A") (pintype "passive"))
      (node (ref "LED86") (pin "A") (pinfunction "A_A") (pintype "passive"))
      (node (ref "LED92") (pin "A") (pinfunction "A_A") (pintype "passive"))
      (node (ref "U4") (pin "17") (pinfunction "CS2_17") (pintype "bidirectional"))
    )
    (net (code "5") (name "CS3_CTRL1") (class "Default")
      (node (ref "LED15") (pin "A") (pinfunction "A_A") (pintype "passive"))
      (node (ref "LED21") (pin "A") (pinfunction "A_A") (pintype "passive"))
      (node (ref "LED27") (pin "A") (pinfunction "A_A") (pintype "passive"))
      (node (ref "LED3") (pin "A") (pinfunction "A_A") (pintype "passive"))
      (node (ref "LED33") (pin "A") (pinfunction "A_A") (pintype "passive"))
      (node (ref "LED39") (pin "A") (pinfunction "A_A") (pintype "passive"))
      (node (ref "LED45") (pin "A") (pinfunction "A_A") (pintype "passive"))
      (node (ref "LED9") (pin "A") (pinfunction "A_A") (pintype "passive"))
      (node (ref "U3") (pin "18") (pinfunction "CS3_18") (pintype "bidirectional"))
    )
    (net (code "6") (name "CS3_CTRL2") (class "Default")
      (node (ref "LED51") (pin "A") (pinfunction "A_A") (pintype "passive"))
      (node (ref "LED57") (pin "A") (pinfunction "A_A") (pintype "passive"))
      (node (ref "LED63") (pin "A") (pinfunction "A_A") (pintype "passive"))
      (node (ref "LED69") (pin "A") (pinfunction "A_A") (pintype "passive"))
      (node (ref "LED75") (pin "A") (pinfunction "A_A") (pintype "passive"))
      (node (ref "LED81") (pin "A") (pinfunction "A_A") (pintype "passive"))
      (node (ref "LED87") (pin "A") (pinfunction "A_A") (pintype "passive"))
      (node (ref "LED93") (pin "A") (pinfunction "A_A") (pintype "passive"))
      (node (ref "U4") (pin "18") (pinfunction "CS3_18") (pintype "bidirectional"))
    )
    (net (code "7") (name "CS4_CTRL1") (class "Default")
      (node (ref "LED10") (pin "A") (pinfunction "A_A") (pintype "passive"))
      (node (ref "LED16") (pin "A") (pinfunction "A_A") (pintype "passive"))
      (node (ref "LED22") (pin "A") (pinfunction "A_A") (pintype "passive"))
      (node (ref "LED28") (pin "A") (pinfunction "A_A") (pintype "passive"))
      (node (ref "LED34") (pin "A") (pinfunction "A_A") (pintype "passive"))
      (node (ref "LED4") (pin "A") (pinfunction "A_A") (pintype "passive"))
      (node (ref "LED40") (pin "A") (pinfunction "A_A") (pintype "passive"))
      (node (ref "LED46") (pin "A") (pinfunction "A_A") (pintype "passive"))
      (node (ref "U3") (pin "19") (pinfunction "CS4_19") (pintype "bidirectional"))
    )
    (net (code "8") (name "CS4_CTRL2") (class "Default")
      (node (ref "LED52") (pin "A") (pinfunction "A_A") (pintype "passive"))
      (node (ref "LED58") (pin "A") (pinfunction "A_A") (pintype "passive"))
      (node (ref "LED64") (pin "A") (pinfunction "A_A") (pintype "passive"))
      (node (ref "LED70") (pin "A") (pinfunction "A_A") (pintype "passive"))
      (node (ref "LED76") (pin "A") (pinfunction "A_A") (pintype "passive"))
      (node (ref "LED82") (pin "A") (pinfunction "A_A") (pintype "passive"))
      (node (ref "LED88") (pin "A") (pinfunction "A_A") (pintype "passive"))
      (node (ref "LED94") (pin "A") (pinfunction "A_A") (pintype "passive"))
      (node (ref "U4") (pin "19") (pinfunction "CS4_19") (pintype "bidirectional"))
    )
    (net (code "9") (name "CS5_CTRL1") (class "Default")
      (node (ref "LED11") (pin "A") (pinfunction "A_A") (pintype "passive"))
      (node (ref "LED17") (pin "A") (pinfunction "A_A") (pintype "passive"))
      (node (ref "LED23") (pin "A") (pinfunction "A_A") (pintype "passive"))
      (node (ref "LED29") (pin "A") (pinfunction "A_A") (pintype "passive"))
      (node (ref "LED35") (pin "A") (pinfunction "A_A") (pintype "passive"))
      (node (ref "LED41") (pin "A") (pinfunction "A_A") (pintype "passive"))
      (node (ref "LED47") (pin "A") (pinfunction "A_A") (pintype "passive"))
      (node (ref "LED5") (pin "A") (pinfunction "A_A") (pintype "passive"))
      (node (ref "U3") (pin "21") (pinfunction "CS5_21") (pintype "bidirectional"))
    )
    (net (code "10") (name "CS5_CTRL2") (class "Default")
      (node (ref "LED53") (pin "A") (pinfunction "A_A") (pintype "passive"))
      (node (ref "LED59") (pin "A") (pinfunction "A_A") (pintype "passive"))
      (node (ref "LED65") (pin "A") (pinfunction "A_A") (pintype "passive"))
      (node (ref "LED71") (pin "A") (pinfunction "A_A") (pintype "passive"))
      (node (ref "LED77") (pin "A") (pinfunction "A_A") (pintype "passive"))
      (node (ref "LED83") (pin "A") (pinfunction "A_A") (pintype "passive"))
      (node (ref "LED89") (pin "A") (pinfunction "A_A") (pintype "passive"))
      (node (ref "LED95") (pin "A") (pinfunction "A_A") (pintype "passive"))
      (node (ref "U4") (pin "21") (pinfunction "CS5_21") (pintype "bidirectional"))
    )
    (net (code "11") (name "CS6_CTRL1") (class "Default")
      (node (ref "LED12") (pin "A") (pinfunction "A_A") (pintype "passive"))
      (node (ref "LED18") (pin "A") (pinfunction "A_A") (pintype "passive"))
      (node (ref "LED24") (pin "A") (pinfunction "A_A") (pintype "passive"))
      (node (ref "LED30") (pin "A") (pinfunction "A_A") (pintype "passive"))
      (node (ref "LED36") (pin "A") (pinfunction "A_A") (pintype "passive"))
      (node (ref "LED42") (pin "A") (pinfunction "A_A") (pintype "passive"))
      (node (ref "LED48") (pin "A") (pinfunction "A_A") (pintype "passive"))
      (node (ref "LED6") (pin "A") (pinfunction "A_A") (pintype "passive"))
      (node (ref "U3") (pin "22") (pinfunction "CS6_22") (pintype "bidirectional"))
    )
    (net (code "12") (name "CS6_CTRL2") (class "Default")
      (node (ref "LED54") (pin "A") (pinfunction "A_A") (pintype "passive"))
      (node (ref "LED60") (pin "A") (pinfunction "A_A") (pintype "passive"))
      (node (ref "LED66") (pin "A") (pinfunction "A_A") (pintype "passive"))
      (node (ref "LED72") (pin "A") (pinfunction "A_A") (pintype "passive"))
      (node (ref "LED78") (pin "A") (pinfunction "A_A") (pintype "passive"))
      (node (ref "LED84") (pin "A") (pinfunction "A_A") (pintype "passive"))
      (node (ref "LED90") (pin "A") (pinfunction "A_A") (pintype "passive"))
      (node (ref "LED96") (pin "A") (pinfunction "A_A") (pintype "passive"))
      (node (ref "U4") (pin "22") (pinfunction "CS6_22") (pintype "bidirectional"))
    )
    (net (code "13") (name "EXTAL") (class "Default")
      (node (ref "C11") (pin "2") (pinfunction "2_2") (pintype "passive"))
      (node (ref "U1") (pin "72") (pinfunction "PTA18_72") (pintype "bidirectional"))
      (node (ref "Y1") (pin "3") (pinfunction "3_3") (pintype "passive"))
    )
    (net (code "14") (name "EXTAL32") (class "Default")
      (node (ref "C33") (pin "1") (pinfunction "1_1") (pintype "passive"))
      (node (ref "U1") (pin "41") (pinfunction "EXTAL32_41") (pintype "passive"))
      (node (ref "Y2") (pin "1") (pinfunction "1_1") (pintype "passive"))
    )
    (net (code "15") (name "GND") (class "Default")
      (node (ref "C1") (pin "2") (pinfunction "2_2") (pintype "passive"))
      (node (ref "C10") (pin "1") (pinfunction "1_1") (pintype "passive"))
      (node (ref "C11") (pin "1") (pinfunction "1_1") (pintype "passive"))
      (node (ref "C12") (pin "1") (pinfunction "1_1") (pintype "passive"))
      (node (ref "C13") (pin "1") (pinfunction "1_1") (pintype "passive"))
      (node (ref "C14") (pin "1") (pinfunction "1_1") (pintype "passive"))
      (node (ref "C15") (pin "2") (pinfunction "2_2") (pintype "passive"))
      (node (ref "C16") (pin "2") (pinfunction "2_2") (pintype "passive"))
      (node (ref "C17") (pin "2") (pinfunction "2_2") (pintype "passive"))
      (node (ref "C18") (pin "2") (pinfunction "2_2") (pintype "passive"))
      (node (ref "C19") (pin "2") (pinfunction "2_2") (pintype "passive"))
      (node (ref "C2") (pin "2") (pinfunction "2_2") (pintype "passive"))
      (node (ref "C20") (pin "2") (pinfunction "2_2") (pintype "passive"))
      (node (ref "C21") (pin "2") (pinfunction "2_2") (pintype "passive"))
      (node (ref "C22") (pin "2") (pinfunction "2_2") (pintype "passive"))
      (node (ref "C23") (pin "-") (pinfunction "-_-") (pintype "passive"))
      (node (ref "C24") (pin "2") (pinfunction "2_2") (pintype "passive"))
      (node (ref "C25") (pin "2") (pinfunction "2_2") (pintype "passive"))
      (node (ref "C26") (pin "2") (pinfunction "2_2") (pintype "passive"))
      (node (ref "C27") (pin "2") (pinfunction "2_2") (pintype "passive"))
      (node (ref "C28") (pin "2") (pinfunction "2_2") (pintype "passive"))
      (node (ref "C29") (pin "2") (pinfunction "2_2") (pintype "passive"))
      (node (ref "C3") (pin "2") (pinfunction "2_2") (pintype "passive"))
      (node (ref "C30") (pin "2") (pinfunction "2_2") (pintype "passive"))
      (node (ref "C31") (pin "-") (pinfunction "-_-") (pintype "passive"))
      (node (ref "C32") (pin "2") (pinfunction "2_2") (pintype "passive"))
      (node (ref "C33") (pin "2") (pinfunction "2_2") (pintype "passive"))
      (node (ref "C34") (pin "2") (pinfunction "2_2") (pintype "passive"))
      (node (ref "C4") (pin "2") (pinfunction "2_2") (pintype "passive"))
      (node (ref "C5") (pin "1") (pinfunction "1_1") (pintype "passive"))
      (node (ref "C6") (pin "1") (pinfunction "1_1") (pintype "passive"))
      (node (ref "C7") (pin "1") (pinfunction "1_1") (pintype "passive"))
      (node (ref "C8") (pin "2") (pinfunction "2_2") (pintype "passive"))
      (node (ref "C9") (pin "1") (pinfunction "1_1") (pintype "passive"))
      (node (ref "J1") (pin "A1_B12") (pinfunction "GND_A1_B12") (pintype "power_in"))
      (node (ref "J1") (pin "B1_A12") (pinfunction "GND_B1_A12") (pintype "power_in"))
      (node (ref "J2") (pin "3") (pinfunction "GND_3") (pintype "bidirectional"))
      (node (ref "J2") (pin "5") (pinfunction "GND2_5") (pintype "bidirectional"))
      (node (ref "L4") (pin "2") (pinfunction "2_2") (pintype "bidirectional"))
      (node (ref "LED97") (pin "C") (pinfunction "C_C") (pintype "passive"))
      (node (ref "LED98") (pin "C") (pinfunction "C_C") (pintype "passive"))
      (node (ref "R14") (pin "1") (pinfunction "1_1") (pintype "passive"))
      (node (ref "R16") (pin "1") (pinfunction "1_1") (pintype "passive"))
      (node (ref "R17") (pin "1") (pinfunction "1_1") (pintype "passive"))
      (node (ref "R18") (pin "1") (pinfunction "1_1") (pintype "passive"))
      (node (ref "R20") (pin "1") (pinfunction "1_1") (pintype "passive"))
      (node (ref "R21") (pin "2") (pinfunction "2_2") (pintype "passive"))
      (node (ref "R6") (pin "1") (pinfunction "1_1") (pintype "passive"))
      (node (ref "R8") (pin "1") (pinfunction "1_1") (pintype "passive"))
      (node (ref "SV1") (pin "4") (pinfunction "4_4") (pintype "passive"))
      (node (ref "SW1") (pin "3") (pinfunction "3_3") (pintype "passive"))
      (node (ref "SW1") (pin "4") (pinfunction "4_4") (pintype "passive"))
      (node (ref "TVS4") (pin "2") (pinfunction "2_2") (pintype "bidirectional"))
      (node (ref "TVS5") (pin "1") (pinfunction "1_1") (pintype "bidirectional"))
      (node (ref "TVS6") (pin "1") (pinfunction "1_1") (pintype "bidirectional"))
      (node (ref "U1") (pin "107") (pinfunction "VSS_3_107") (pintype "power_in"))
      (node (ref "U1") (pin "121") (pinfunction "VSS_4_121") (pintype "power_in"))
      (node (ref "U1") (pin "134") (pinfunction "VSS_134") (pintype "power_in"))
      (node (ref "U1") (pin "17") (pinfunction "VSS_3_17") (pintype "power_in"))
      (node (ref "U1") (pin "18") (pinfunction "VSS_7_18") (pintype "power_in"))
      (node (ref "U1") (pin "33") (pinfunction "VREFL_33") (pintype "power_in"))
      (node (ref "U1") (pin "34") (pinfunction "VSSA_34") (pintype "power_in"))
      (node (ref "U1") (pin "44") (pinfunction "VSS_5_44") (pintype "power_in"))
      (node (ref "U1") (pin "57") (pinfunction "VSS_6_57") (pintype "power_in"))
      (node (ref "U1") (pin "6") (pinfunction "VSS_2_6") (pintype "power_in"))
      (node (ref "U1") (pin "71") (pinfunction "VSS_71") (pintype "power_in"))
      (node (ref "U1") (pin "93") (pinfunction "VSS_2_93") (pintype "power_in"))
      (node (ref "U3") (pin "12") (pinfunction "PGND_2_12") (pintype "bidirectional"))
      (node (ref "U3") (pin "34") (pinfunction "AGND_34") (pintype "bidirectional"))
      (node (ref "U3") (pin "43") (pinfunction "ADDR1_43") (pintype "bidirectional"))
      (node (ref "U3") (pin "44") (pinfunction "ADDR2_44") (pintype "bidirectional"))
      (node (ref "U3") (pin "48") (pinfunction "GND_48") (pintype "bidirectional"))
      (node (ref "U3") (pin "5") (pinfunction "PGND_5") (pintype "bidirectional"))
      (node (ref "U3") (pin "PAD") (pinfunction "PAD_GND_PAD") (pintype "bidirectional"))
      (node (ref "U4") (pin "12") (pinfunction "PGND_2_12") (pintype "bidirectional"))
      (node (ref "U4") (pin "34") (pinfunction "AGND_34") (pintype "bidirectional"))
      (node (ref "U4") (pin "48") (pinfunction "GND_48") (pintype "bidirectional"))
      (node (ref "U4") (pin "5") (pinfunction "PGND_5") (pintype "bidirectional"))
      (node (ref "U4") (pin "PAD") (pinfunction "PAD_GND_PAD") (pintype "bidirectional"))
      (node (ref "U5") (pin "4") (pinfunction "GND_4") (pintype "bidirectional"))
      (node (ref "U5") (pin "5") (pinfunction "A2_5") (pintype "bidirectional"))
      (node (ref "U5") (pin "6") (pinfunction "A1_6") (pintype "bidirectional"))
      (node (ref "U5") (pin "7") (pinfunction "A0_7") (pintype "bidirectional"))
      (node (ref "U6") (pin "6") (pinfunction "GND_6") (pintype "bidirectional"))
      (node (ref "U6") (pin "7") (pinfunction "GND_2_7") (pintype "bidirectional"))
      (node (ref "Y1") (pin "2") (pinfunction "GND_2") (pintype "power_in"))
      (node (ref "Y1") (pin "4") (pinfunction "GND_4") (pintype "power_in"))
    )
    (net (code "16") (name "I2C2_SCL") (class "Default")
      (node (ref "R5") (pin "1") (pinfunction "1_1") (pintype "passive"))
      (node (ref "TP5") (pin "TP") (pinfunction "TP_TP") (pintype "input"))
      (node (ref "U1") (pin "64") (pinfunction "PTA12_64") (pintype "bidirectional"))
      (node (ref "U3") (pin "42") (pinfunction "SCL_42") (pintype "bidirectional"))
      (node (ref "U4") (pin "42") (pinfunction "SCL_42") (pintype "bidirectional"))
      (node (ref "U5") (pin "2") (pinfunction "SCL_2") (pintype "bidirectional"))
    )
    (net (code "17") (name "I2C2_SDA") (class "Default")
      (node (ref "R4") (pin "1") (pinfunction "1_1") (pintype "passive"))
      (node (ref "TP4") (pin "TP") (pinfunction "TP_TP") (pintype "input"))
      (node (ref "U1") (pin "65") (pinfunction "PTA13/LLWU_P4_65") (pintype "bidirectional"))
      (node (ref "U3") (pin "41") (pinfunction "SDA_41") (pintype "bidirectional"))
      (node (ref "U4") (pin "41") (pinfunction "SDA_41") (pintype "bidirectional"))
      (node (ref "U5") (pin "1") (pinfunction "SDA_1") (pintype "bidirectional"))
    )
    (net (code "18") (name "IICRST_LED_CTRL1") (class "Default")
      (node (ref "R6") (pin "2") (pinfunction "2_2") (pintype "passive"))
      (node (ref "U3") (pin "47") (pinfunction "IICRST_47") (pintype "bidirectional"))
    )
    (net (code "19") (name "IICRST_LED_CTRL_2") (class "Default")
      (node (ref "R14") (pin "2") (pinfunction "2_2") (pintype "passive"))
      (node (ref "U4") (pin "47") (pinfunction "IICRST_47") (pintype "bidirectional"))
    )
    (net (code "20") (name "INTB_LED_CTRL_1") (class "Default")
      (node (ref "R7") (pin "1") (pinfunction "1_1") (pintype "passive"))
      (node (ref "U1") (pin "8") (pinfunction "PTE5_8") (pintype "bidirectional"))
      (node (ref "U3") (pin "45") (pinfunction "INTB_45") (pintype "bidirectional"))
    )
    (net (code "21") (name "INTB_LED_CTRL_2") (class "Default")
      (node (ref "R15") (pin "1") (pinfunction "1_1") (pintype "passive"))
      (node (ref "U1") (pin "9") (pinfunction "PTE6_9") (pintype "bidirectional"))
      (node (ref "U4") (pin "45") (pinfunction "INTB_45") (pintype "bidirectional"))
    )
    (net (code "22") (name "JTAG_TCLK{slash}SWD_CLK") (class "Default")
      (node (ref "J2") (pin "4") (pinfunction "TCK_4") (pintype "bidirectional"))
      (node (ref "U1") (pin "50") (pinfunction "PTA0_50") (pintype "bidirectional"))
    )
    (net (code "23") (name "JTAG_TDI") (class "Default")
      (node (ref "J2") (pin "8") (pinfunction "TDI_8") (pintype "bidirectional"))
      (node (ref "U1") (pin "51") (pinfunction "PTA1_51") (pintype "bidirectional"))
    )
    (net (code "24") (name "JTAG_TDO{slash}TRACE_SWO") (class "Default")
      (node (ref "J2") (pin "6") (pinfunction "TDO_6") (pintype "bidirectional"))
      (node (ref "U1") (pin "52") (pinfunction "PTA2_52") (pintype "bidirectional"))
    )
    (net (code "25") (name "JTAG_TMS{slash}SWD_DIO") (class "Default")
      (node (ref "J2") (pin "2") (pinfunction "TMS_2") (pintype "bidirectional"))
      (node (ref "U1") (pin "53") (pinfunction "PTA3_53") (pintype "bidirectional"))
    )
    (net (code "26") (name "LED_CTRL_SYNC") (class "Default")
      (node (ref "U3") (pin "40") (pinfunction "SYNC_40") (pintype "bidirectional"))
      (node (ref "U4") (pin "40") (pinfunction "SYNC_40") (pintype "bidirectional"))
    )
    (net (code "27") (name "MATRIX_C1") (class "Default")
      (node (ref "S1") (pin "3") (pinfunction "3_3") (pintype "passive"))
      (node (ref "S1") (pin "4") (pinfunction "4_4") (pintype "passive"))
      (node (ref "S3") (pin "3") (pinfunction "3_3") (pintype "passive"))
      (node (ref "S3") (pin "4") (pinfunction "4_4") (pintype "passive"))
      (node (ref "U1") (pin "11") (pinfunction "PTE8_11") (pintype "bidirectional"))
    )
    (net (code "28") (name "MATRIX_C2") (class "Default")
      (node (ref "S2") (pin "3") (pinfunction "3_3") (pintype "passive"))
      (node (ref "S2") (pin "4") (pinfunction "4_4") (pintype "passive"))
      (node (ref "S4") (pin "3") (pinfunction "3_3") (pintype "passive"))
      (node (ref "S4") (pin "4") (pinfunction "4_4") (pintype "passive"))
      (node (ref "U1") (pin "15") (pinfunction "PTE12_15") (pintype "bidirectional"))
    )
    (net (code "29") (name "MATRIX_R1") (class "Default")
      (node (ref "D1") (pin "3") (pinfunction "C_3") (pintype "passive"))
      (node (ref "D2") (pin "3") (pinfunction "C_3") (pintype "passive"))
      (node (ref "U1") (pin "3") (pinfunction "PTE2/LLWU_P1_3") (pintype "bidirectional"))
    )
    (net (code "30") (name "MATRIX_R2") (class "Default")
      (node (ref "D3") (pin "3") (pinfunction "C_3") (pintype "passive"))
      (node (ref "D4") (pin "3") (pinfunction "C_3") (pintype "passive"))
      (node (ref "U1") (pin "4") (pinfunction "PTE3_4") (pintype "bidirectional"))
    )
    (net (code "31") (name "MCU_LED1") (class "Default")
      (node (ref "R2") (pin "2") (pinfunction "2_2") (pintype "passive"))
      (node (ref "U1") (pin "45") (pinfunction "PTE24_45") (pintype "bidirectional"))
    )
    (net (code "32") (name "MCU_LED2") (class "Default")
      (node (ref "R3") (pin "2") (pinfunction "2_2") (pintype "passive"))
      (node (ref "U1") (pin "46") (pinfunction "PTE25_46") (pintype "bidirectional"))
    )
    (net (code "33") (name "NMI") (class "Default")
      (node (ref "C15") (pin "1") (pinfunction "1_1") (pintype "passive"))
      (node (ref "R11") (pin "1") (pinfunction "1_1") (pintype "passive"))
      (node (ref "U1") (pin "54") (pinfunction "PTA4/LLWU_P3_54") (pintype "bidirectional"))
    )
    (net (code "34") (name "Net-(D1-A)") (class "Default")
      (node (ref "D1") (pin "1") (pinfunction "A_1") (pintype "passive"))
      (node (ref "S1") (pin "1") (pinfunction "1_1") (pintype "passive"))
      (node (ref "S1") (pin "2") (pinfunction "2_2") (pintype "passive"))
    )
    (net (code "35") (name "Net-(D2-A)") (class "Default")
      (node (ref "D2") (pin "1") (pinfunction "A_1") (pintype "passive"))
      (node (ref "S2") (pin "1") (pinfunction "1_1") (pintype "passive"))
      (node (ref "S2") (pin "2") (pinfunction "2_2") (pintype "passive"))
    )
    (net (code "36") (name "Net-(D3-A)") (class "Default")
      (node (ref "D3") (pin "1") (pinfunction "A_1") (pintype "passive"))
      (node (ref "S3") (pin "1") (pinfunction "1_1") (pintype "passive"))
      (node (ref "S3") (pin "2") (pinfunction "2_2") (pintype "passive"))
    )
    (net (code "37") (name "Net-(D4-A)") (class "Default")
      (node (ref "D4") (pin "1") (pinfunction "A_1") (pintype "passive"))
      (node (ref "S4") (pin "1") (pinfunction "1_1") (pintype "passive"))
      (node (ref "S4") (pin "2") (pinfunction "2_2") (pintype "passive"))
    )
    (net (code "38") (name "Net-(J1-CC1)") (class "Default")
      (node (ref "J1") (pin "A5") (pinfunction "CC1_A5") (pintype "bidirectional"))
      (node (ref "R20") (pin "2") (pinfunction "2_2") (pintype "passive"))
    )
    (net (code "39") (name "Net-(J1-CC2)") (class "Default")
      (node (ref "J1") (pin "B5") (pinfunction "CC2_B5") (pintype "bidirectional"))
      (node (ref "R21") (pin "1") (pinfunction "1_1") (pintype "passive"))
    )
    (net (code "40") (name "Net-(J1-SHELL_GND-PadS1)") (class "Default")
      (node (ref "J1") (pin "S1") (pinfunction "SHELL_GND_S1") (pintype "power_in"))
      (node (ref "J1") (pin "S2") (pinfunction "SHELL_GND_S2") (pintype "power_in"))
      (node (ref "J1") (pin "S3") (pinfunction "SHELL_GND_S3") (pintype "power_in"))
      (node (ref "J1") (pin "S4") (pinfunction "SHELL_GND_S4") (pintype "power_in"))
      (node (ref "L4") (pin "1") (pinfunction "1_1") (pintype "bidirectional"))
    )
    (net (code "41") (name "Net-(LED97-PadA)") (class "Default")
      (node (ref "LED97") (pin "A") (pinfunction "A_A") (pintype "passive"))
      (node (ref "R2") (pin "1") (pinfunction "1_1") (pintype "passive"))
    )
    (net (code "42") (name "Net-(LED98-PadA)") (class "Default")
      (node (ref "LED98") (pin "A") (pinfunction "A_A") (pintype "passive"))
      (node (ref "R3") (pin "1") (pinfunction "1_1") (pintype "passive"))
    )
    (net (code "43") (name "Net-(U3-ISET)") (class "Default")
      (node (ref "R17") (pin "2") (pinfunction "2_2") (pintype "passive"))
      (node (ref "U3") (pin "35") (pinfunction "ISET_35") (pintype "bidirectional"))
    )
    (net (code "44") (name "Net-(U4-ISET)") (class "Default")
      (node (ref "R18") (pin "2") (pinfunction "2_2") (pintype "passive"))
      (node (ref "U4") (pin "35") (pinfunction "ISET_35") (pintype "bidirectional"))
    )
    (net (code "45") (name "Net-(U5-VDD)") (class "Default")
      (node (ref "R9") (pin "1") (pinfunction "1_1") (pintype "passive"))
      (node (ref "U5") (pin "8") (pinfunction "VDD_8") (pintype "bidirectional"))
    )
    (net (code "46") (name "RESET") (class "Default")
      (node (ref "C1") (pin "1") (pinfunction "1_1") (pintype "passive"))
      (node (ref "J2") (pin "10") (pinfunction "NRESET_10") (pintype "bidirectional"))
      (node (ref "R1") (pin "1") (pinfunction "1_1") (pintype "passive"))
      (node (ref "SW1") (pin "1") (pinfunction "1_1") (pintype "passive"))
      (node (ref "SW1") (pin "2") (pinfunction "2_2") (pintype "passive"))
      (node (ref "U1") (pin "74") (pinfunction "RESET_B_74") (pintype "passive"))
    )
    (net (code "47") (name "SDB_LED_CTRL_1") (class "Default")
      (node (ref "R8") (pin "2") (pinfunction "2_2") (pintype "passive"))
      (node (ref "U1") (pin "7") (pinfunction "PTE4/LLWU_P2_7") (pintype "bidirectional"))
      (node (ref "U3") (pin "46") (pinfunction "SDB_46") (pintype "bidirectional"))
    )
    (net (code "48") (name "SDB_LED_CTRL_2") (class "Default")
      (node (ref "R16") (pin "2") (pinfunction "2_2") (pintype "passive"))
      (node (ref "U1") (pin "10") (pinfunction "PTE7_10") (pintype "bidirectional"))
      (node (ref "U4") (pin "46") (pinfunction "SDB_46") (pintype "bidirectional"))
    )
    (net (code "49") (name "SW1_CTRL1") (class "Default")
      (node (ref "LED1") (pin "K") (pinfunction "C_K") (pintype "passive"))
      (node (ref "LED2") (pin "K") (pinfunction "C_K") (pintype "passive"))
      (node (ref "LED3") (pin "K") (pinfunction "C_K") (pintype "passive"))
      (node (ref "LED4") (pin "K") (pinfunction "C_K") (pintype "passive"))
      (node (ref "LED5") (pin "K") (pinfunction "C_K") (pintype "passive"))
      (node (ref "LED6") (pin "K") (pinfunction "C_K") (pintype "passive"))
      (node (ref "U3") (pin "2") (pinfunction "SW1_2") (pintype "bidirectional"))
    )
    (net (code "50") (name "SW1_CTRL2") (class "Default")
      (node (ref "LED49") (pin "K") (pinfunction "C_K") (pintype "passive"))
      (node (ref "LED50") (pin "K") (pinfunction "C_K") (pintype "passive"))
      (node (ref "LED51") (pin "K") (pinfunction "C_K") (pintype "passive"))
      (node (ref "LED52") (pin "K") (pinfunction "C_K") (pintype "passive"))
      (node (ref "LED53") (pin "K") (pinfunction "C_K") (pintype "passive"))
      (node (ref "LED54") (pin "K") (pinfunction "C_K") (pintype "passive"))
      (node (ref "U4") (pin "2") (pinfunction "SW1_2") (pintype "bidirectional"))
    )
    (net (code "51") (name "SW2_CTRL1") (class "Default")
      (node (ref "LED10") (pin "K") (pinfunction "C_K") (pintype "passive"))
      (node (ref "LED11") (pin "K") (pinfunction "C_K") (pintype "passive"))
      (node (ref "LED12") (pin "K") (pinfunction "C_K") (pintype "passive"))
      (node (ref "LED7") (pin "K") (pinfunction "C_K") (pintype "passive"))
      (node (ref "LED8") (pin "K") (pinfunction "C_K") (pintype "passive"))
      (node (ref "LED9") (pin "K") (pinfunction "C_K") (pintype "passive"))
      (node (ref "U3") (pin "3") (pinfunction "SW2_3") (pintype "bidirectional"))
    )
    (net (code "52") (name "SW2_CTRL2") (class "Default")
      (node (ref "LED55") (pin "K") (pinfunction "C_K") (pintype "passive"))
      (node (ref "LED56") (pin "K") (pinfunction "C_K") (pintype "passive"))
      (node (ref "LED57") (pin "K") (pinfunction "C_K") (pintype "passive"))
      (node (ref "LED58") (pin "K") (pinfunction "C_K") (pintype "passive"))
      (node (ref "LED59") (pin "K") (pinfunction "C_K") (pintype "passive"))
      (node (ref "LED60") (pin "K") (pinfunction "C_K") (pintype "passive"))
      (node (ref "U4") (pin "3") (pinfunction "SW2_3") (pintype "bidirectional"))
    )
    (net (code "53") (name "SW3_CTRL1") (class "Default")
      (node (ref "LED13") (pin "K") (pinfunction "C_K") (pintype "passive"))
      (node (ref "LED14") (pin "K") (pinfunction "C_K") (pintype "passive"))
      (node (ref "LED15") (pin "K") (pinfunction "C_K") (pintype "passive"))
      (node (ref "LED16") (pin "K") (pinfunction "C_K") (pintype "passive"))
      (node (ref "LED17") (pin "K") (pinfunction "C_K") (pintype "passive"))
      (node (ref "LED18") (pin "K") (pinfunction "C_K") (pintype "passive"))
      (node (ref "U3") (pin "4") (pinfunction "SW3_4") (pintype "bidirectional"))
    )
    (net (code "54") (name "SW3_CTRL2") (class "Default")
      (node (ref "LED61") (pin "K") (pinfunction "C_K") (pintype "passive"))
      (node (ref "LED62") (pin "K") (pinfunction "C_K") (pintype "passive"))
      (node (ref "LED63") (pin "K") (pinfunction "C_K") (pintype "passive"))
      (node (ref "LED64") (pin "K") (pinfunction "C_K") (pintype "passive"))
      (node (ref "LED65") (pin "K") (pinfunction "C_K") (pintype "passive"))
      (node (ref "LED66") (pin "K") (pinfunction "C_K") (pintype "passive"))
      (node (ref "U4") (pin "4") (pinfunction "SW3_4") (pintype "bidirectional"))
    )
    (net (code "55") (name "SW4_CTRL1") (class "Default")
      (node (ref "LED19") (pin "K") (pinfunction "C_K") (pintype "passive"))
      (node (ref "LED20") (pin "K") (pinfunction "C_K") (pintype "passive"))
      (node (ref "LED21") (pin "K") (pinfunction "C_K") (pintype "passive"))
      (node (ref "LED22") (pin "K") (pinfunction "C_K") (pintype "passive"))
      (node (ref "LED23") (pin "K") (pinfunction "C_K") (pintype "passive"))
      (node (ref "LED24") (pin "K") (pinfunction "C_K") (pintype "passive"))
      (node (ref "U3") (pin "6") (pinfunction "SW4_6") (pintype "bidirectional"))
    )
    (net (code "56") (name "SW4_CTRL2") (class "Default")
      (node (ref "LED67") (pin "K") (pinfunction "C_K") (pintype "passive"))
      (node (ref "LED68") (pin "K") (pinfunction "C_K") (pintype "passive"))
      (node (ref "LED69") (pin "K") (pinfunction "C_K") (pintype "passive"))
      (node (ref "LED70") (pin "K") (pinfunction "C_K") (pintype "passive"))
      (node (ref "LED71") (pin "K") (pinfunction "C_K") (pintype "passive"))
      (node (ref "LED72") (pin "K") (pinfunction "C_K") (pintype "passive"))
      (node (ref "U4") (pin "6") (pinfunction "SW4_6") (pintype "bidirectional"))
    )
    (net (code "57") (name "SW5_CTRL1") (class "Default")
      (node (ref "LED25") (pin "K") (pinfunction "C_K") (pintype "passive"))
      (node (ref "LED26") (pin "K") (pinfunction "C_K") (pintype "passive"))
      (node (ref "LED27") (pin "K") (pinfunction "C_K") (pintype "passive"))
      (node (ref "LED28") (pin "K") (pinfunction "C_K") (pintype "passive"))
      (node (ref "LED29") (pin "K") (pinfunction "C_K") (pintype "passive"))
      (node (ref "LED30") (pin "K") (pinfunction "C_K") (pintype "passive"))
      (node (ref "U3") (pin "7") (pinfunction "SW5_7") (pintype "bidirectional"))
    )
    (net (code "58") (name "SW5_CTRL2") (class "Default")
      (node (ref "LED73") (pin "K") (pinfunction "C_K") (pintype "passive"))
      (node (ref "LED74") (pin "K") (pinfunction "C_K") (pintype "passive"))
      (node (ref "LED75") (pin "K") (pinfunction "C_K") (pintype "passive"))
      (node (ref "LED76") (pin "K") (pinfunction "C_K") (pintype "passive"))
      (node (ref "LED77") (pin "K") (pinfunction "C_K") (pintype "passive"))
      (node (ref "LED78") (pin "K") (pinfunction "C_K") (pintype "passive"))
      (node (ref "U4") (pin "7") (pinfunction "SW5_7") (pintype "bidirectional"))
    )
    (net (code "59") (name "SW6_CTRL1") (class "Default")
      (node (ref "LED31") (pin "K") (pinfunction "C_K") (pintype "passive"))
      (node (ref "LED32") (pin "K") (pinfunction "C_K") (pintype "passive"))
      (node (ref "LED33") (pin "K") (pinfunction "C_K") (pintype "passive"))
      (node (ref "LED34") (pin "K") (pinfunction "C_K") (pintype "passive"))
      (node (ref "LED35") (pin "K") (pinfunction "C_K") (pintype "passive"))
      (node (ref "LED36") (pin "K") (pinfunction "C_K") (pintype "passive"))
      (node (ref "U3") (pin "8") (pinfunction "SW6_8") (pintype "bidirectional"))
    )
    (net (code "60") (name "SW6_CTRL2") (class "Default")
      (node (ref "LED79") (pin "K") (pinfunction "C_K") (pintype "passive"))
      (node (ref "LED80") (pin "K") (pinfunction "C_K") (pintype "passive"))
      (node (ref "LED81") (pin "K") (pinfunction "C_K") (pintype "passive"))
      (node (ref "LED82") (pin "K") (pinfunction "C_K") (pintype "passive"))
      (node (ref "LED83") (pin "K") (pinfunction "C_K") (pintype "passive"))
      (node (ref "LED84") (pin "K") (pinfunction "C_K") (pintype "passive"))
      (node (ref "U4") (pin "8") (pinfunction "SW6_8") (pintype "bidirectional"))
    )
    (net (code "61") (name "SW7_CTRL1") (class "Default")
      (node (ref "LED37") (pin "K") (pinfunction "C_K") (pintype "passive"))
      (node (ref "LED38") (pin "K") (pinfunction "C_K") (pintype "passive"))
      (node (ref "LED39") (pin "K") (pinfunction "C_K") (pintype "passive"))
      (node (ref "LED40") (pin "K") (pinfunction "C_K") (pintype "passive"))
      (node (ref "LED41") (pin "K") (pinfunction "C_K") (pintype "passive"))
      (node (ref "LED42") (pin "K") (pinfunction "C_K") (pintype "passive"))
      (node (ref "U3") (pin "9") (pinfunction "SW7_9") (pintype "bidirectional"))
    )
    (net (code "62") (name "SW7_CTRL2") (class "Default")
      (node (ref "LED85") (pin "K") (pinfunction "C_K") (pintype "passive"))
      (node (ref "LED86") (pin "K") (pinfunction "C_K") (pintype "passive"))
      (node (ref "LED87") (pin "K") (pinfunction "C_K") (pintype "passive"))
      (node (ref "LED88") (pin "K") (pinfunction "C_K") (pintype "passive"))
      (node (ref "LED89") (pin "K") (pinfunction "C_K") (pintype "passive"))
      (node (ref "LED90") (pin "K") (pinfunction "C_K") (pintype "passive"))
      (node (ref "U4") (pin "9") (pinfunction "SW7_9") (pintype "bidirectional"))
    )
    (net (code "63") (name "SW8_CTRL1") (class "Default")
      (node (ref "LED43") (pin "K") (pinfunction "C_K") (pintype "passive"))
      (node (ref "LED44") (pin "K") (pinfunction "C_K") (pintype "passive"))
      (node (ref "LED45") (pin "K") (pinfunction "C_K") (pintype "passive"))
      (node (ref "LED46") (pin "K") (pinfunction "C_K") (pintype "passive"))
      (node (ref "LED47") (pin "K") (pinfunction "C_K") (pintype "passive"))
      (node (ref "LED48") (pin "K") (pinfunction "C_K") (pintype "passive"))
      (node (ref "U3") (pin "10") (pinfunction "SW8_10") (pintype "bidirectional"))
    )
    (net (code "64") (name "SW8_CTRL2") (class "Default")
      (node (ref "LED91") (pin "K") (pinfunction "C_K") (pintype "passive"))
      (node (ref "LED92") (pin "K") (pinfunction "C_K") (pintype "passive"))
      (node (ref "LED93") (pin "K") (pinfunction "C_K") (pintype "passive"))
      (node (ref "LED94") (pin "K") (pinfunction "C_K") (pintype "passive"))
      (node (ref "LED95") (pin "K") (pinfunction "C_K") (pintype "passive"))
      (node (ref "LED96") (pin "K") (pinfunction "C_K") (pintype "passive"))
      (node (ref "U4") (pin "10") (pinfunction "SW8_10") (pintype "bidirectional"))
    )
    (net (code "65") (name "TEMP_ALERT") (class "Default")
      (node (ref "U1") (pin "13") (pinfunction "PTE10_13") (pintype "bidirectional"))
      (node (ref "U5") (pin "3") (pinfunction "ALERT_3") (pintype "bidirectional"))
    )
    (net (code "66") (name "UART0_RX") (class "Default")
      (node (ref "SV1") (pin "3") (pinfunction "3_3") (pintype "passive"))
      (node (ref "U1") (pin "95") (pinfunction "PTB16_95") (pintype "bidirectional"))
    )
    (net (code "67") (name "UART0_TX") (class "Default")
      (node (ref "SV1") (pin "2") (pinfunction "2_2") (pintype "passive"))
      (node (ref "U1") (pin "96") (pinfunction "PTB17_96") (pintype "bidirectional"))
    )
    (net (code "68") (name "USB_MCU_N") (class "Default")
      (node (ref "R19") (pin "2") (pinfunction "2_2") (pintype "passive"))
      (node (ref "U1") (pin "20") (pinfunction "USB0_DM_20") (pintype "bidirectional"))
    )
    (net (code "69") (name "USB_MCU_P") (class "Default")
      (node (ref "R10") (pin "2") (pinfunction "2_2") (pintype "passive"))
      (node (ref "U1") (pin "19") (pinfunction "USB0_DP_19") (pintype "bidirectional"))
    )
    (net (code "70") (name "USB_N") (class "Default")
      (node (ref "J1") (pin "A7") (pinfunction "DN1_A7") (pintype "bidirectional"))
      (node (ref "J1") (pin "B7") (pinfunction "DN2_B7") (pintype "bidirectional"))
      (node (ref "R19") (pin "1") (pinfunction "1_1") (pintype "passive"))
      (node (ref "TVS5") (pin "2") (pinfunction "2_2") (pintype "bidirectional"))
    )
    (net (code "71") (name "USB_P") (class "Default")
      (node (ref "J1") (pin "A6") (pinfunction "DP1_A6") (pintype "bidirectional"))
      (node (ref "J1") (pin "B6") (pinfunction "DP2_B6") (pintype "bidirectional"))
      (node (ref "R10") (pin "1") (pinfunction "1_1") (pintype "passive"))
      (node (ref "TVS6") (pin "2") (pinfunction "2_2") (pintype "bidirectional"))
    )
    (net (code "72") (name "VBUS") (class "Default")
      (node (ref "J1") (pin "A4_B9") (pinfunction "VBUS_A4_B9") (pintype "power_in"))
      (node (ref "J1") (pin "B4_A9") (pinfunction "VBUS_B4_A9") (pintype "power_in"))
      (node (ref "L3") (pin "1") (pinfunction "1_1") (pintype "bidirectional"))
      (node (ref "TP2") (pin "TP") (pinfunction "TP_TP") (pintype "input"))
      (node (ref "TVS4") (pin "1") (pinfunction "1_1") (pintype "bidirectional"))
    )
    (net (code "73") (name "VDD_3V3") (class "Default")
      (node (ref "C2") (pin "1") (pinfunction "1_1") (pintype "passive"))
      (node (ref "C22") (pin "1") (pinfunction "1_1") (pintype "passive"))
      (node (ref "C3") (pin "1") (pinfunction "1_1") (pintype "passive"))
      (node (ref "C30") (pin "1") (pinfunction "1_1") (pintype "passive"))
      (node (ref "C32") (pin "1") (pinfunction "1_1") (pintype "passive"))
      (node (ref "C4") (pin "1") (pinfunction "1_1") (pintype "passive"))
      (node (ref "C5") (pin "2") (pinfunction "2_2") (pintype "passive"))
      (node (ref "C6") (pin "2") (pinfunction "2_2") (pintype "passive"))
      (node (ref "C7") (pin "2") (pinfunction "2_2") (pintype "passive"))
      (node (ref "C8") (pin "1") (pinfunction "1_1") (pintype "passive"))
      (node (ref "C9") (pin "2") (pinfunction "2_2") (pintype "passive"))
      (node (ref "J2") (pin "1") (pinfunction "VCC_1") (pintype "bidirectional"))
      (node (ref "R1") (pin "2") (pinfunction "2_2") (pintype "passive"))
      (node (ref "R11") (pin "2") (pinfunction "2_2") (pintype "passive"))
      (node (ref "R15") (pin "2") (pinfunction "2_2") (pintype "passive"))
      (node (ref "R4") (pin "2") (pinfunction "2_2") (pintype "passive"))
      (node (ref "R5") (pin "2") (pinfunction "2_2") (pintype "passive"))
      (node (ref "R7") (pin "2") (pinfunction "2_2") (pintype "passive"))
      (node (ref "R9") (pin "2") (pinfunction "2_2") (pintype "passive"))
      (node (ref "SJ1") (pin "2") (pinfunction "2_2") (pintype "passive"))
      (node (ref "SV1") (pin "1") (pinfunction "1_1") (pintype "passive"))
      (node (ref "TP3") (pin "TP") (pinfunction "TP_TP") (pintype "input"))
      (node (ref "U1") (pin "108") (pinfunction "VDD_3_108") (pintype "power_in"))
      (node (ref "U1") (pin "122") (pinfunction "VDD_4_122") (pintype "power_in"))
      (node (ref "U1") (pin "135") (pinfunction "VDD_135") (pintype "power_in"))
      (node (ref "U1") (pin "16") (pinfunction "VDD_3_16") (pintype "power_in"))
      (node (ref "U1") (pin "31") (pinfunction "VDDA_31") (pintype "power_in"))
      (node (ref "U1") (pin "32") (pinfunction "VREFH_32") (pintype "power_in"))
      (node (ref "U1") (pin "42") (pinfunction "VBAT_42") (pintype "power_in"))
      (node (ref "U1") (pin "43") (pinfunction "VDD_4_43") (pintype "power_in"))
      (node (ref "U1") (pin "5") (pinfunction "VDD_2_5") (pintype "power_in"))
      (node (ref "U1") (pin "56") (pinfunction "VDD_5_56") (pintype "power_in"))
      (node (ref "U1") (pin "70") (pinfunction "VDD_70") (pintype "power_in"))
      (node (ref "U1") (pin "94") (pinfunction "VDD_2_94") (pintype "power_in"))
      (node (ref "U3") (pin "39") (pinfunction "VIO_39") (pintype "bidirectional"))
      (node (ref "U4") (pin "39") (pinfunction "VIO_39") (pintype "bidirectional"))
    )
    (net (code "74") (name "VFERRITE") (class "Default")
      (node (ref "D5") (pin "2") (pinfunction "P$2_2") (pintype "bidirectional"))
      (node (ref "L3") (pin "2") (pinfunction "2_2") (pintype "bidirectional"))
    )
    (net (code "75") (name "VLDO_33") (class "Default")
      (node (ref "C14") (pin "2") (pinfunction "2_2") (pintype "passive"))
      (node (ref "SJ1") (pin "1") (pinfunction "1_1") (pintype "passive"))
      (node (ref "U6") (pin "1") (pinfunction "VOUT_1") (pintype "bidirectional"))
    )
    (net (code "76") (name "VOUT_33") (class "Default")
      (node (ref "C12") (pin "2") (pinfunction "2_2") (pintype "passive"))
      (node (ref "SJ1") (pin "3") (pinfunction "3_3") (pintype "passive"))
      (node (ref "U1") (pin "21") (pinfunction "VOUT33_21") (pintype "power_in"))
    )
    (net (code "77") (name "VSYS_5V") (class "Default")
      (node (ref "C13") (pin "2") (pinfunction "2_2") (pintype "passive"))
      (node (ref "C16") (pin "1") (pinfunction "1_1") (pintype "passive"))
      (node (ref "C17") (pin "1") (pinfunction "1_1") (pintype "passive"))
      (node (ref "C18") (pin "1") (pinfunction "1_1") (pintype "passive"))
      (node (ref "C19") (pin "1") (pinfunction "1_1") (pintype "passive"))
      (node (ref "C20") (pin "1") (pinfunction "1_1") (pintype "passive"))
      (node (ref "C21") (pin "1") (pinfunction "1_1") (pintype "passive"))
      (node (ref "C23") (pin "+") (pinfunction "+_+") (pintype "passive"))
      (node (ref "C24") (pin "1") (pinfunction "1_1") (pintype "passive"))
      (node (ref "C25") (pin "1") (pinfunction "1_1") (pintype "passive"))
      (node (ref "C26") (pin "1") (pinfunction "1_1") (pintype "passive"))
      (node (ref "C27") (pin "1") (pinfunction "1_1") (pintype "passive"))
      (node (ref "C28") (pin "1") (pinfunction "1_1") (pintype "passive"))
      (node (ref "C29") (pin "1") (pinfunction "1_1") (pintype "passive"))
      (node (ref "C31") (pin "+") (pinfunction "+_+") (pintype "passive"))
      (node (ref "D5") (pin "1") (pinfunction "P$1_1") (pintype "bidirectional"))
      (node (ref "TP1") (pin "TP") (pinfunction "TP_TP") (pintype "input"))
      (node (ref "U1") (pin "22") (pinfunction "VREGIN_22") (pintype "power_in"))
      (node (ref "U3") (pin "20") (pinfunction "PVCC_20") (pintype "bidirectional"))
      (node (ref "U3") (pin "29") (pinfunction "PVCC_2_29") (pintype "bidirectional"))
      (node (ref "U3") (pin "37") (pinfunction "AVCC_37") (pintype "bidirectional"))
      (node (ref "U3") (pin "38") (pinfunction "DVCC_38") (pintype "bidirectional"))
      (node (ref "U4") (pin "20") (pinfunction "PVCC_20") (pintype "bidirectional"))
      (node (ref "U4") (pin "29") (pinfunction "PVCC_2_29") (pintype "bidirectional"))
      (node (ref "U4") (pin "37") (pinfunction "AVCC_37") (pintype "bidirectional"))
      (node (ref "U4") (pin "38") (pinfunction "DVCC_38") (pintype "bidirectional"))
      (node (ref "U4") (pin "43") (pinfunction "ADDR1_43") (pintype "bidirectional"))
      (node (ref "U4") (pin "44") (pinfunction "ADDR2_44") (pintype "bidirectional"))
      (node (ref "U6") (pin "5") (pinfunction "EN_5") (pintype "bidirectional"))
      (node (ref "U6") (pin "8") (pinfunction "VIN_8") (pintype "bidirectional"))
    )
    (net (code "78") (name "XTAL") (class "Default")
      (node (ref "C10") (pin "2") (pinfunction "2_2") (pintype "passive"))
      (node (ref "U1") (pin "73") (pinfunction "PTA19_73") (pintype "bidirectional"))
      (node (ref "Y1") (pin "1") (pinfunction "1_1") (pintype "passive"))
    )
    (net (code "79") (name "XTAL32") (class "Default")
      (node (ref "C34") (pin "1") (pinfunction "1_1") (pintype "passive"))
      (node (ref "U1") (pin "40") (pinfunction "XTAL32_40") (pintype "passive"))
      (node (ref "Y2") (pin "2") (pinfunction "2_2") (pintype "passive"))
    )
    (net (code "80") (name "unconnected-(J1-SBU1-PadA8)") (class "Default")
      (node (ref "J1") (pin "A8") (pinfunction "SBU1_A8") (pintype "bidirectional"))
    )
    (net (code "81") (name "unconnected-(J1-SBU2-PadB8)") (class "Default")
      (node (ref "J1") (pin "B8") (pinfunction "SBU2_B8") (pintype "bidirectional"))
    )
    (net (code "82") (name "unconnected-(J2-GNDDETECT-Pad9)") (class "Default")
      (node (ref "J2") (pin "9") (pinfunction "GNDDETECT_9") (pintype "bidirectional"))
    )
    (net (code "83") (name "unconnected-(J2-KEY-Pad7)") (class "Default")
      (node (ref "J2") (pin "7") (pinfunction "KEY_7") (pintype "bidirectional"))
    )
    (net (code "84") (name "unconnected-(U1A-ADC0_DM0{slash}ADC1_DM3-Pad28)") (class "Default")
      (node (ref "U1") (pin "28") (pinfunction "ADC0_DM0/ADC1_DM3_28") (pintype "bidirectional"))
    )
    (net (code "85") (name "unconnected-(U1A-ADC0_DM1-Pad24)") (class "Default")
      (node (ref "U1") (pin "24") (pinfunction "ADC0_DM1_24") (pintype "bidirectional"))
    )
    (net (code "86") (name "unconnected-(U1A-ADC0_DP0{slash}ADC1_DP3-Pad27)") (class "Default")
      (node (ref "U1") (pin "27") (pinfunction "ADC0_DP0/ADC1_DP3_27") (pintype "bidirectional"))
    )
    (net (code "87") (name "unconnected-(U1A-ADC0_DP1-Pad23)") (class "Default")
      (node (ref "U1") (pin "23") (pinfunction "ADC0_DP1_23") (pintype "bidirectional"))
    )
    (net (code "88") (name "unconnected-(U1A-ADC0_SE16{slash}CMP1_IN2{slash}ADC0_SE21-Pad36)") (class "Default")
      (node (ref "U1") (pin "36") (pinfunction "ADC0_SE16/CMP1_IN2/ADC0_SE21_36") (pintype "bidirectional"))
    )
    (net (code "89") (name "unconnected-(U1A-ADC1_DM0{slash}ADC0_DM3-Pad30)") (class "Default")
      (node (ref "U1") (pin "30") (pinfunction "ADC1_DM0/ADC0_DM3_30") (pintype "bidirectional"))
    )
    (net (code "90") (name "unconnected-(U1A-ADC1_DM1-Pad26)") (class "Default")
      (node (ref "U1") (pin "26") (pinfunction "ADC1_DM1_26") (pintype "bidirectional"))
    )
    (net (code "91") (name "unconnected-(U1A-ADC1_DP0{slash}ADC0_DP3-Pad29)") (class "Default")
      (node (ref "U1") (pin "29") (pinfunction "ADC1_DP0/ADC0_DP3_29") (pintype "bidirectional"))
    )
    (net (code "92") (name "unconnected-(U1A-ADC1_DP1-Pad25)") (class "Default")
      (node (ref "U1") (pin "25") (pinfunction "ADC1_DP1_25") (pintype "bidirectional"))
    )
    (net (code "93") (name "unconnected-(U1A-ADC1_SE16{slash}CMP2_IN2{slash}ADC0_SE22-Pad35)") (class "Default")
      (node (ref "U1") (pin "35") (pinfunction "ADC1_SE16/CMP2_IN2/ADC0_SE22_35") (pintype "bidirectional"))
    )
    (net (code "94") (name "unconnected-(U1A-DAC0_OUT{slash}CMP1_IN3{slash}ADC0_SE23-Pad38)") (class "Default")
      (node (ref "U1") (pin "38") (pinfunction "DAC0_OUT/CMP1_IN3/ADC0_SE23_38") (pintype "bidirectional"))
    )
    (net (code "95") (name "unconnected-(U1A-DAC1_OUT{slash}CMP0_IN4{slash}CMP2_IN3{slash}ADC1_SE23-Pad39)") (class "Default")
      (node (ref "U1") (pin "39") (pinfunction "DAC1_OUT/CMP0_IN4/CMP2_IN3/ADC1_SE23_39") (pintype "bidirectional"))
    )
    (net (code "96") (name "unconnected-(U1A-DAC1_OUT{slash}CMP1_IN5{slash}CMP0_IN5{slash}ADC1_SE18-Pad37)") (class "Default")
      (node (ref "U1") (pin "37") (pinfunction "DAC1_OUT/CMP1_IN5/CMP0_IN5/ADC1_SE18_37") (pintype "bidirectional"))
    )
    (net (code "97") (name "unconnected-(U1A-PTA5-Pad55)") (class "Default")
      (node (ref "U1") (pin "55") (pinfunction "PTA5_55") (pintype "bidirectional"))
    )
    (net (code "98") (name "unconnected-(U1A-PTA6-Pad58)") (class "Default")
      (node (ref "U1") (pin "58") (pinfunction "PTA6_58") (pintype "bidirectional"))
    )
    (net (code "99") (name "unconnected-(U1A-PTA7-Pad59)") (class "Default")
      (node (ref "U1") (pin "59") (pinfunction "PTA7_59") (pintype "bidirectional"))
    )
    (net (code "100") (name "unconnected-(U1A-PTA8-Pad60)") (class "Default")
      (node (ref "U1") (pin "60") (pinfunction "PTA8_60") (pintype "bidirectional"))
    )
    (net (code "101") (name "unconnected-(U1A-PTA9-Pad61)") (class "Default")
      (node (ref "U1") (pin "61") (pinfunction "PTA9_61") (pintype "bidirectional"))
    )
    (net (code "102") (name "unconnected-(U1A-PTA10-Pad62)") (class "Default")
      (node (ref "U1") (pin "62") (pinfunction "PTA10_62") (pintype "bidirectional"))
    )
    (net (code "103") (name "unconnected-(U1A-PTA11-Pad63)") (class "Default")
      (node (ref "U1") (pin "63") (pinfunction "PTA11_63") (pintype "bidirectional"))
    )
    (net (code "104") (name "unconnected-(U1A-PTA14-Pad66)") (class "Default")
      (node (ref "U1") (pin "66") (pinfunction "PTA14_66") (pintype "bidirectional"))
    )
    (net (code "105") (name "unconnected-(U1A-PTA15-Pad67)") (class "Default")
      (node (ref "U1") (pin "67") (pinfunction "PTA15_67") (pintype "bidirectional"))
    )
    (net (code "106") (name "unconnected-(U1A-PTA16-Pad68)") (class "Default")
      (node (ref "U1") (pin "68") (pinfunction "PTA16_68") (pintype "bidirectional"))
    )
    (net (code "107") (name "unconnected-(U1A-PTA17-Pad69)") (class "Default")
      (node (ref "U1") (pin "69") (pinfunction "PTA17_69") (pintype "bidirectional"))
    )
    (net (code "108") (name "unconnected-(U1A-PTE0-Pad1)") (class "Default")
      (node (ref "U1") (pin "1") (pinfunction "PTE0_1") (pintype "bidirectional"))
    )
    (net (code "109") (name "unconnected-(U1A-PTE1{slash}LLWU_P0-Pad2)") (class "Default")
      (node (ref "U1") (pin "2") (pinfunction "PTE1/LLWU_P0_2") (pintype "bidirectional"))
    )
    (net (code "110") (name "unconnected-(U1A-PTE9-Pad12)") (class "Default")
      (node (ref "U1") (pin "12") (pinfunction "PTE9_12") (pintype "bidirectional"))
    )
    (net (code "111") (name "unconnected-(U1A-PTE11-Pad14)") (class "Default")
      (node (ref "U1") (pin "14") (pinfunction "PTE11_14") (pintype "bidirectional"))
    )
    (net (code "112") (name "unconnected-(U1A-PTE26-Pad47)") (class "Default")
      (node (ref "U1") (pin "47") (pinfunction "PTE26_47") (pintype "bidirectional"))
    )
    (net (code "113") (name "unconnected-(U1A-PTE27-Pad48)") (class "Default")
      (node (ref "U1") (pin "48") (pinfunction "PTE27_48") (pintype "bidirectional"))
    )
    (net (code "114") (name "unconnected-(U1A-PTE28-Pad49)") (class "Default")
      (node (ref "U1") (pin "49") (pinfunction "PTE28_49") (pintype "bidirectional"))
    )
    (net (code "115") (name "unconnected-(U1B-PTA24-Pad75)") (class "Default")
      (node (ref "U1") (pin "75") (pinfunction "PTA24_75") (pintype "bidirectional"))
    )
    (net (code "116") (name "unconnected-(U1B-PTA25-Pad76)") (class "Default")
      (node (ref "U1") (pin "76") (pinfunction "PTA25_76") (pintype "bidirectional"))
    )
    (net (code "117") (name "unconnected-(U1B-PTA26-Pad77)") (class "Default")
      (node (ref "U1") (pin "77") (pinfunction "PTA26_77") (pintype "bidirectional"))
    )
    (net (code "118") (name "unconnected-(U1B-PTA27-Pad78)") (class "Default")
      (node (ref "U1") (pin "78") (pinfunction "PTA27_78") (pintype "bidirectional"))
    )
    (net (code "119") (name "unconnected-(U1B-PTA28-Pad79)") (class "Default")
      (node (ref "U1") (pin "79") (pinfunction "PTA28_79") (pintype "bidirectional"))
    )
    (net (code "120") (name "unconnected-(U1B-PTA29-Pad80)") (class "Default")
      (node (ref "U1") (pin "80") (pinfunction "PTA29_80") (pintype "bidirectional"))
    )
    (net (code "121") (name "unconnected-(U1B-PTB0{slash}LLWU_P5-Pad81)") (class "Default")
      (node (ref "U1") (pin "81") (pinfunction "PTB0/LLWU_P5_81") (pintype "bidirectional"))
    )
    (net (code "122") (name "unconnected-(U1B-PTB1-Pad82)") (class "Default")
      (node (ref "U1") (pin "82") (pinfunction "PTB1_82") (pintype "bidirectional"))
    )
    (net (code "123") (name "unconnected-(U1B-PTB2-Pad83)") (class "Default")
      (node (ref "U1") (pin "83") (pinfunction "PTB2_83") (pintype "bidirectional"))
    )
    (net (code "124") (name "unconnected-(U1B-PTB3-Pad84)") (class "Default")
      (node (ref "U1") (pin "84") (pinfunction "PTB3_84") (pintype "bidirectional"))
    )
    (net (code "125") (name "unconnected-(U1B-PTB4-Pad85)") (class "Default")
      (node (ref "U1") (pin "85") (pinfunction "PTB4_85") (pintype "bidirectional"))
    )
    (net (code "126") (name "unconnected-(U1B-PTB5-Pad86)") (class "Default")
      (node (ref "U1") (pin "86") (pinfunction "PTB5_86") (pintype "bidirectional"))
    )
    (net (code "127") (name "unconnected-(U1B-PTB6-Pad87)") (class "Default")
      (node (ref "U1") (pin "87") (pinfunction "PTB6_87") (pintype "bidirectional"))
    )
    (net (code "128") (name "unconnected-(U1B-PTB7-Pad88)") (class "Default")
      (node (ref "U1") (pin "88") (pinfunction "PTB7_88") (pintype "bidirectional"))
    )
    (net (code "129") (name "unconnected-(U1B-PTB8-Pad89)") (class "Default")
      (node (ref "U1") (pin "89") (pinfunction "PTB8_89") (pintype "bidirectional"))
    )
    (net (code "130") (name "unconnected-(U1B-PTB9-Pad90)") (class "Default")
      (node (ref "U1") (pin "90") (pinfunction "PTB9_90") (pintype "bidirectional"))
    )
    (net (code "131") (name "unconnected-(U1B-PTB10-Pad91)") (class "Default")
      (node (ref "U1") (pin "91") (pinfunction "PTB10_91") (pintype "bidirectional"))
    )
    (net (code "132") (name "unconnected-(U1B-PTB11-Pad92)") (class "Default")
      (node (ref "U1") (pin "92") (pinfunction "PTB11_92") (pintype "bidirectional"))
    )
    (net (code "133") (name "unconnected-(U1B-PTB18-Pad97)") (class "Default")
      (node (ref "U1") (pin "97") (pinfunction "PTB18_97") (pintype "bidirectional"))
    )
    (net (code "134") (name "unconnected-(U1B-PTB19-Pad98)") (class "Default")
      (node (ref "U1") (pin "98") (pinfunction "PTB19_98") (pintype "bidirectional"))
    )
    (net (code "135") (name "unconnected-(U1B-PTB20-Pad99)") (class "Default")
      (node (ref "U1") (pin "99") (pinfunction "PTB20_99") (pintype "bidirectional"))
    )
    (net (code "136") (name "unconnected-(U1B-PTB21-Pad100)") (class "Default")
      (node (ref "U1") (pin "100") (pinfunction "PTB21_100") (pintype "bidirectional"))
    )
    (net (code "137") (name "unconnected-(U1B-PTB22-Pad101)") (class "Default")
      (node (ref "U1") (pin "101") (pinfunction "PTB22_101") (pintype "bidirectional"))
    )
    (net (code "138") (name "unconnected-(U1B-PTB23-Pad102)") (class "Default")
      (node (ref "U1") (pin "102") (pinfunction "PTB23_102") (pintype "bidirectional"))
    )
    (net (code "139") (name "unconnected-(U1B-PTC0-Pad103)") (class "Default")
      (node (ref "U1") (pin "103") (pinfunction "PTC0_103") (pintype "bidirectional"))
    )
    (net (code "140") (name "unconnected-(U1B-PTC1{slash}LLWU_P6-Pad104)") (class "Default")
      (node (ref "U1") (pin "104") (pinfunction "PTC1/LLWU_P6_104") (pintype "bidirectional"))
    )
    (net (code "141") (name "unconnected-(U1B-PTC2-Pad105)") (class "Default")
      (node (ref "U1") (pin "105") (pinfunction "PTC2_105") (pintype "bidirectional"))
    )
    (net (code "142") (name "unconnected-(U1B-PTC3{slash}LLWU_P7-Pad106)") (class "Default")
      (node (ref "U1") (pin "106") (pinfunction "PTC3/LLWU_P7_106") (pintype "bidirectional"))
    )
    (net (code "143") (name "unconnected-(U1B-PTC4{slash}LLWU_P8-Pad109)") (class "Default")
      (node (ref "U1") (pin "109") (pinfunction "PTC4/LLWU_P8_109") (pintype "bidirectional"))
    )
    (net (code "144") (name "unconnected-(U1B-PTC5{slash}LLWU_P9-Pad110)") (class "Default")
      (node (ref "U1") (pin "110") (pinfunction "PTC5/LLWU_P9_110") (pintype "bidirectional"))
    )
    (net (code "145") (name "unconnected-(U1B-PTC6{slash}LLWU_P10-Pad111)") (class "Default")
      (node (ref "U1") (pin "111") (pinfunction "PTC6/LLWU_P10_111") (pintype "bidirectional"))
    )
    (net (code "146") (name "unconnected-(U1B-PTC7-Pad112)") (class "Default")
      (node (ref "U1") (pin "112") (pinfunction "PTC7_112") (pintype "bidirectional"))
    )
    (net (code "147") (name "unconnected-(U1B-PTC8-Pad113)") (class "Default")
      (node (ref "U1") (pin "113") (pinfunction "PTC8_113") (pintype "bidirectional"))
    )
    (net (code "148") (name "unconnected-(U1B-PTC9-Pad114)") (class "Default")
      (node (ref "U1") (pin "114") (pinfunction "PTC9_114") (pintype "bidirectional"))
    )
    (net (code "149") (name "unconnected-(U1B-PTC10-Pad115)") (class "Default")
      (node (ref "U1") (pin "115") (pinfunction "PTC10_115") (pintype "bidirectional"))
    )
    (net (code "150") (name "unconnected-(U1B-PTC11{slash}LLWU_P11-Pad116)") (class "Default")
      (node (ref "U1") (pin "116") (pinfunction "PTC11/LLWU_P11_116") (pintype "bidirectional"))
    )
    (net (code "151") (name "unconnected-(U1B-PTC12-Pad117)") (class "Default")
      (node (ref "U1") (pin "117") (pinfunction "PTC12_117") (pintype "bidirectional"))
    )
    (net (code "152") (name "unconnected-(U1B-PTC13-Pad118)") (class "Default")
      (node (ref "U1") (pin "118") (pinfunction "PTC13_118") (pintype "bidirectional"))
    )
    (net (code "153") (name "unconnected-(U1B-PTC14-Pad119)") (class "Default")
      (node (ref "U1") (pin "119") (pinfunction "PTC14_119") (pintype "bidirectional"))
    )
    (net (code "154") (name "unconnected-(U1B-PTC15-Pad120)") (class "Default")
      (node (ref "U1") (pin "120") (pinfunction "PTC15_120") (pintype "bidirectional"))
    )
    (net (code "155") (name "unconnected-(U1B-PTC16-Pad123)") (class "Default")
      (node (ref "U1") (pin "123") (pinfunction "PTC16_123") (pintype "bidirectional"))
    )
    (net (code "156") (name "unconnected-(U1B-PTC17-Pad124)") (class "Default")
      (node (ref "U1") (pin "124") (pinfunction "PTC17_124") (pintype "bidirectional"))
    )
    (net (code "157") (name "unconnected-(U1B-PTC18-Pad125)") (class "Default")
      (node (ref "U1") (pin "125") (pinfunction "PTC18_125") (pintype "bidirectional"))
    )
    (net (code "158") (name "unconnected-(U1B-PTC19-Pad126)") (class "Default")
      (node (ref "U1") (pin "126") (pinfunction "PTC19_126") (pintype "bidirectional"))
    )
    (net (code "159") (name "unconnected-(U1B-PTD0{slash}LLWU_P12-Pad127)") (class "Default")
      (node (ref "U1") (pin "127") (pinfunction "PTD0/LLWU_P12_127") (pintype "bidirectional"))
    )
    (net (code "160") (name "unconnected-(U1B-PTD1-Pad128)") (class "Default")
      (node (ref "U1") (pin "128") (pinfunction "PTD1_128") (pintype "bidirectional"))
    )
    (net (code "161") (name "unconnected-(U1B-PTD2{slash}LLWU_P13-Pad129)") (class "Default")
      (node (ref "U1") (pin "129") (pinfunction "PTD2/LLWU_P13_129") (pintype "bidirectional"))
    )
    (net (code "162") (name "unconnected-(U1B-PTD3-Pad130)") (class "Default")
      (node (ref "U1") (pin "130") (pinfunction "PTD3_130") (pintype "bidirectional"))
    )
    (net (code "163") (name "unconnected-(U1B-PTD4{slash}LLWU_P14-Pad131)") (class "Default")
      (node (ref "U1") (pin "131") (pinfunction "PTD4/LLWU_P14_131") (pintype "bidirectional"))
    )
    (net (code "164") (name "unconnected-(U1B-PTD5-Pad132)") (class "Default")
      (node (ref "U1") (pin "132") (pinfunction "PTD5_132") (pintype "bidirectional"))
    )
    (net (code "165") (name "unconnected-(U1B-PTD6{slash}LLWU_P15-Pad133)") (class "Default")
      (node (ref "U1") (pin "133") (pinfunction "PTD6/LLWU_P15_133") (pintype "bidirectional"))
    )
    (net (code "166") (name "unconnected-(U1B-PTD7-Pad136)") (class "Default")
      (node (ref "U1") (pin "136") (pinfunction "PTD7_136") (pintype "bidirectional"))
    )
    (net (code "167") (name "unconnected-(U1B-PTD8-Pad137)") (class "Default")
      (node (ref "U1") (pin "137") (pinfunction "PTD8_137") (pintype "bidirectional"))
    )
    (net (code "168") (name "unconnected-(U1B-PTD9-Pad138)") (class "Default")
      (node (ref "U1") (pin "138") (pinfunction "PTD9_138") (pintype "bidirectional"))
    )
    (net (code "169") (name "unconnected-(U1B-PTD10-Pad139)") (class "Default")
      (node (ref "U1") (pin "139") (pinfunction "PTD10_139") (pintype "bidirectional"))
    )
    (net (code "170") (name "unconnected-(U1B-PTD11-Pad140)") (class "Default")
      (node (ref "U1") (pin "140") (pinfunction "PTD11_140") (pintype "bidirectional"))
    )
    (net (code "171") (name "unconnected-(U1B-PTD12-Pad141)") (class "Default")
      (node (ref "U1") (pin "141") (pinfunction "PTD12_141") (pintype "bidirectional"))
    )
    (net (code "172") (name "unconnected-(U1B-PTD13-Pad142)") (class "Default")
      (node (ref "U1") (pin "142") (pinfunction "PTD13_142") (pintype "bidirectional"))
    )
    (net (code "173") (name "unconnected-(U1B-PTD14-Pad143)") (class "Default")
      (node (ref "U1") (pin "143") (pinfunction "PTD14_143") (pintype "bidirectional"))
    )
    (net (code "174") (name "unconnected-(U1B-PTD15-Pad144)") (class "Default")
      (node (ref "U1") (pin "144") (pinfunction "PTD15_144") (pintype "bidirectional"))
    )
    (net (code "175") (name "unconnected-(U3-CS7-Pad23)") (class "Default")
      (node (ref "U3") (pin "23") (pinfunction "CS7_23") (pintype "bidirectional"))
    )
    (net (code "176") (name "unconnected-(U3-CS8-Pad24)") (class "Default")
      (node (ref "U3") (pin "24") (pinfunction "CS8_24") (pintype "bidirectional"))
    )
    (net (code "177") (name "unconnected-(U3-CS9-Pad25)") (class "Default")
      (node (ref "U3") (pin "25") (pinfunction "CS9_25") (pintype "bidirectional"))
    )
    (net (code "178") (name "unconnected-(U3-CS10-Pad26)") (class "Default")
      (node (ref "U3") (pin "26") (pinfunction "CS10_26") (pintype "bidirectional"))
    )
    (net (code "179") (name "unconnected-(U3-CS11-Pad27)") (class "Default")
      (node (ref "U3") (pin "27") (pinfunction "CS11_27") (pintype "bidirectional"))
    )
    (net (code "180") (name "unconnected-(U3-CS12-Pad28)") (class "Default")
      (node (ref "U3") (pin "28") (pinfunction "CS12_28") (pintype "bidirectional"))
    )
    (net (code "181") (name "unconnected-(U3-CS13-Pad30)") (class "Default")
      (node (ref "U3") (pin "30") (pinfunction "CS13_30") (pintype "bidirectional"))
    )
    (net (code "182") (name "unconnected-(U3-CS14-Pad31)") (class "Default")
      (node (ref "U3") (pin "31") (pinfunction "CS14_31") (pintype "bidirectional"))
    )
    (net (code "183") (name "unconnected-(U3-CS15-Pad32)") (class "Default")
      (node (ref "U3") (pin "32") (pinfunction "CS15_32") (pintype "bidirectional"))
    )
    (net (code "184") (name "unconnected-(U3-CS16-Pad33)") (class "Default")
      (node (ref "U3") (pin "33") (pinfunction "CS16_33") (pintype "bidirectional"))
    )
    (net (code "185") (name "unconnected-(U3-NC-Pad1)") (class "Default")
      (node (ref "U3") (pin "1") (pinfunction "NC_1") (pintype "no_connect"))
    )
    (net (code "186") (name "unconnected-(U3-NC_2-Pad36)") (class "Default")
      (node (ref "U3") (pin "36") (pinfunction "NC_2_36") (pintype "no_connect"))
    )
    (net (code "187") (name "unconnected-(U3-SW9-Pad11)") (class "Default")
      (node (ref "U3") (pin "11") (pinfunction "SW9_11") (pintype "bidirectional"))
    )
    (net (code "188") (name "unconnected-(U3-SW10-Pad13)") (class "Default")
      (node (ref "U3") (pin "13") (pinfunction "SW10_13") (pintype "bidirectional"))
    )
    (net (code "189") (name "unconnected-(U3-SW11-Pad14)") (class "Default")
      (node (ref "U3") (pin "14") (pinfunction "SW11_14") (pintype "bidirectional"))
    )
    (net (code "190") (name "unconnected-(U3-SW12-Pad15)") (class "Default")
      (node (ref "U3") (pin "15") (pinfunction "SW12_15") (pintype "bidirectional"))
    )
    (net (code "191") (name "unconnected-(U4-CS7-Pad23)") (class "Default")
      (node (ref "U4") (pin "23") (pinfunction "CS7_23") (pintype "bidirectional"))
    )
    (net (code "192") (name "unconnected-(U4-CS8-Pad24)") (class "Default")
      (node (ref "U4") (pin "24") (pinfunction "CS8_24") (pintype "bidirectional"))
    )
    (net (code "193") (name "unconnected-(U4-CS9-Pad25)") (class "Default")
      (node (ref "U4") (pin "25") (pinfunction "CS9_25") (pintype "bidirectional"))
    )
    (net (code "194") (name "unconnected-(U4-CS10-Pad26)") (class "Default")
      (node (ref "U4") (pin "26") (pinfunction "CS10_26") (pintype "bidirectional"))
    )
    (net (code "195") (name "unconnected-(U4-CS11-Pad27)") (class "Default")
      (node (ref "U4") (pin "27") (pinfunction "CS11_27") (pintype "bidirectional"))
    )
    (net (code "196") (name "unconnected-(U4-CS12-Pad28)") (class "Default")
      (node (ref "U4") (pin "28") (pinfunction "CS12_28") (pintype "bidirectional"))
    )
    (net (code "197") (name "unconnected-(U4-CS13-Pad30)") (class "Default")
      (node (ref "U4") (pin "30") (pinfunction "CS13_30") (pintype "bidirectional"))
    )
    (net (code "198") (name "unconnected-(U4-CS14-Pad31)") (class "Default")
      (node (ref "U4") (pin "31") (pinfunction "CS14_31") (pintype "bidirectional"))
    )
    (net (code "199") (name "unconnected-(U4-CS15-Pad32)") (class "Default")
      (node (ref "U4") (pin "32") (pinfunction "CS15_32") (pintype "bidirectional"))
    )
    (net (code "200") (name "unconnected-(U4-CS16-Pad33)") (class "Default")
      (node (ref "U4") (pin "33") (pinfunction "CS16_33") (pintype "bidirectional"))
    )
    (net (code "201") (name "unconnected-(U4-NC-Pad1)") (class "Default")
      (node (ref "U4") (pin "1") (pinfunction "NC_1") (pintype "no_connect"))
    )
    (net (code "202") (name "unconnected-(U4-NC_2-Pad36)") (class "Default")
      (node (ref "U4") (pin "36") (pinfunction "NC_2_36") (pintype "no_connect"))
    )
    (net (code "203") (name "unconnected-(U4-SW9-Pad11)") (class "Default")
      (node (ref "U4") (pin "11") (pinfunction "SW9_11") (pintype "bidirectional"))
    )
    (net (code "204") (name "unconnected-(U4-SW10-Pad13)") (class "Default")
      (node (ref "U4") (pin "13") (pinfunction "SW10_13") (pintype "bidirectional"))
    )
    (net (code "205") (name "unconnected-(U4-SW11-Pad14)") (class "Default")
      (node (ref "U4") (pin "14") (pinfunction "SW11_14") (pintype "bidirectional"))
    )
    (net (code "206") (name "unconnected-(U4-SW12-Pad15)") (class "Default")
      (node (ref "U4") (pin "15") (pinfunction "SW12_15") (pintype "bidirectional"))
    )
    (net (code "207") (name "unconnected-(U6-NC-Pad2)") (class "Default")
      (node (ref "U6") (pin "2") (pinfunction "NC_2") (pintype "no_connect"))
    )
    (net (code "208") (name "unconnected-(U6-NC_2-Pad3)") (class "Default")
      (node (ref "U6") (pin "3") (pinfunction "NC_2_3") (pintype "no_connect"))
    )
    (net (code "209") (name "unconnected-(U6-NC_3-Pad4)") (class "Default")
      (node (ref "U6") (pin "4") (pinfunction "NC_3_4") (pintype "no_connect"))
    )
  )
)
